# homeboard19.net
KiCad netlist of a schematic drawn in EAGLE
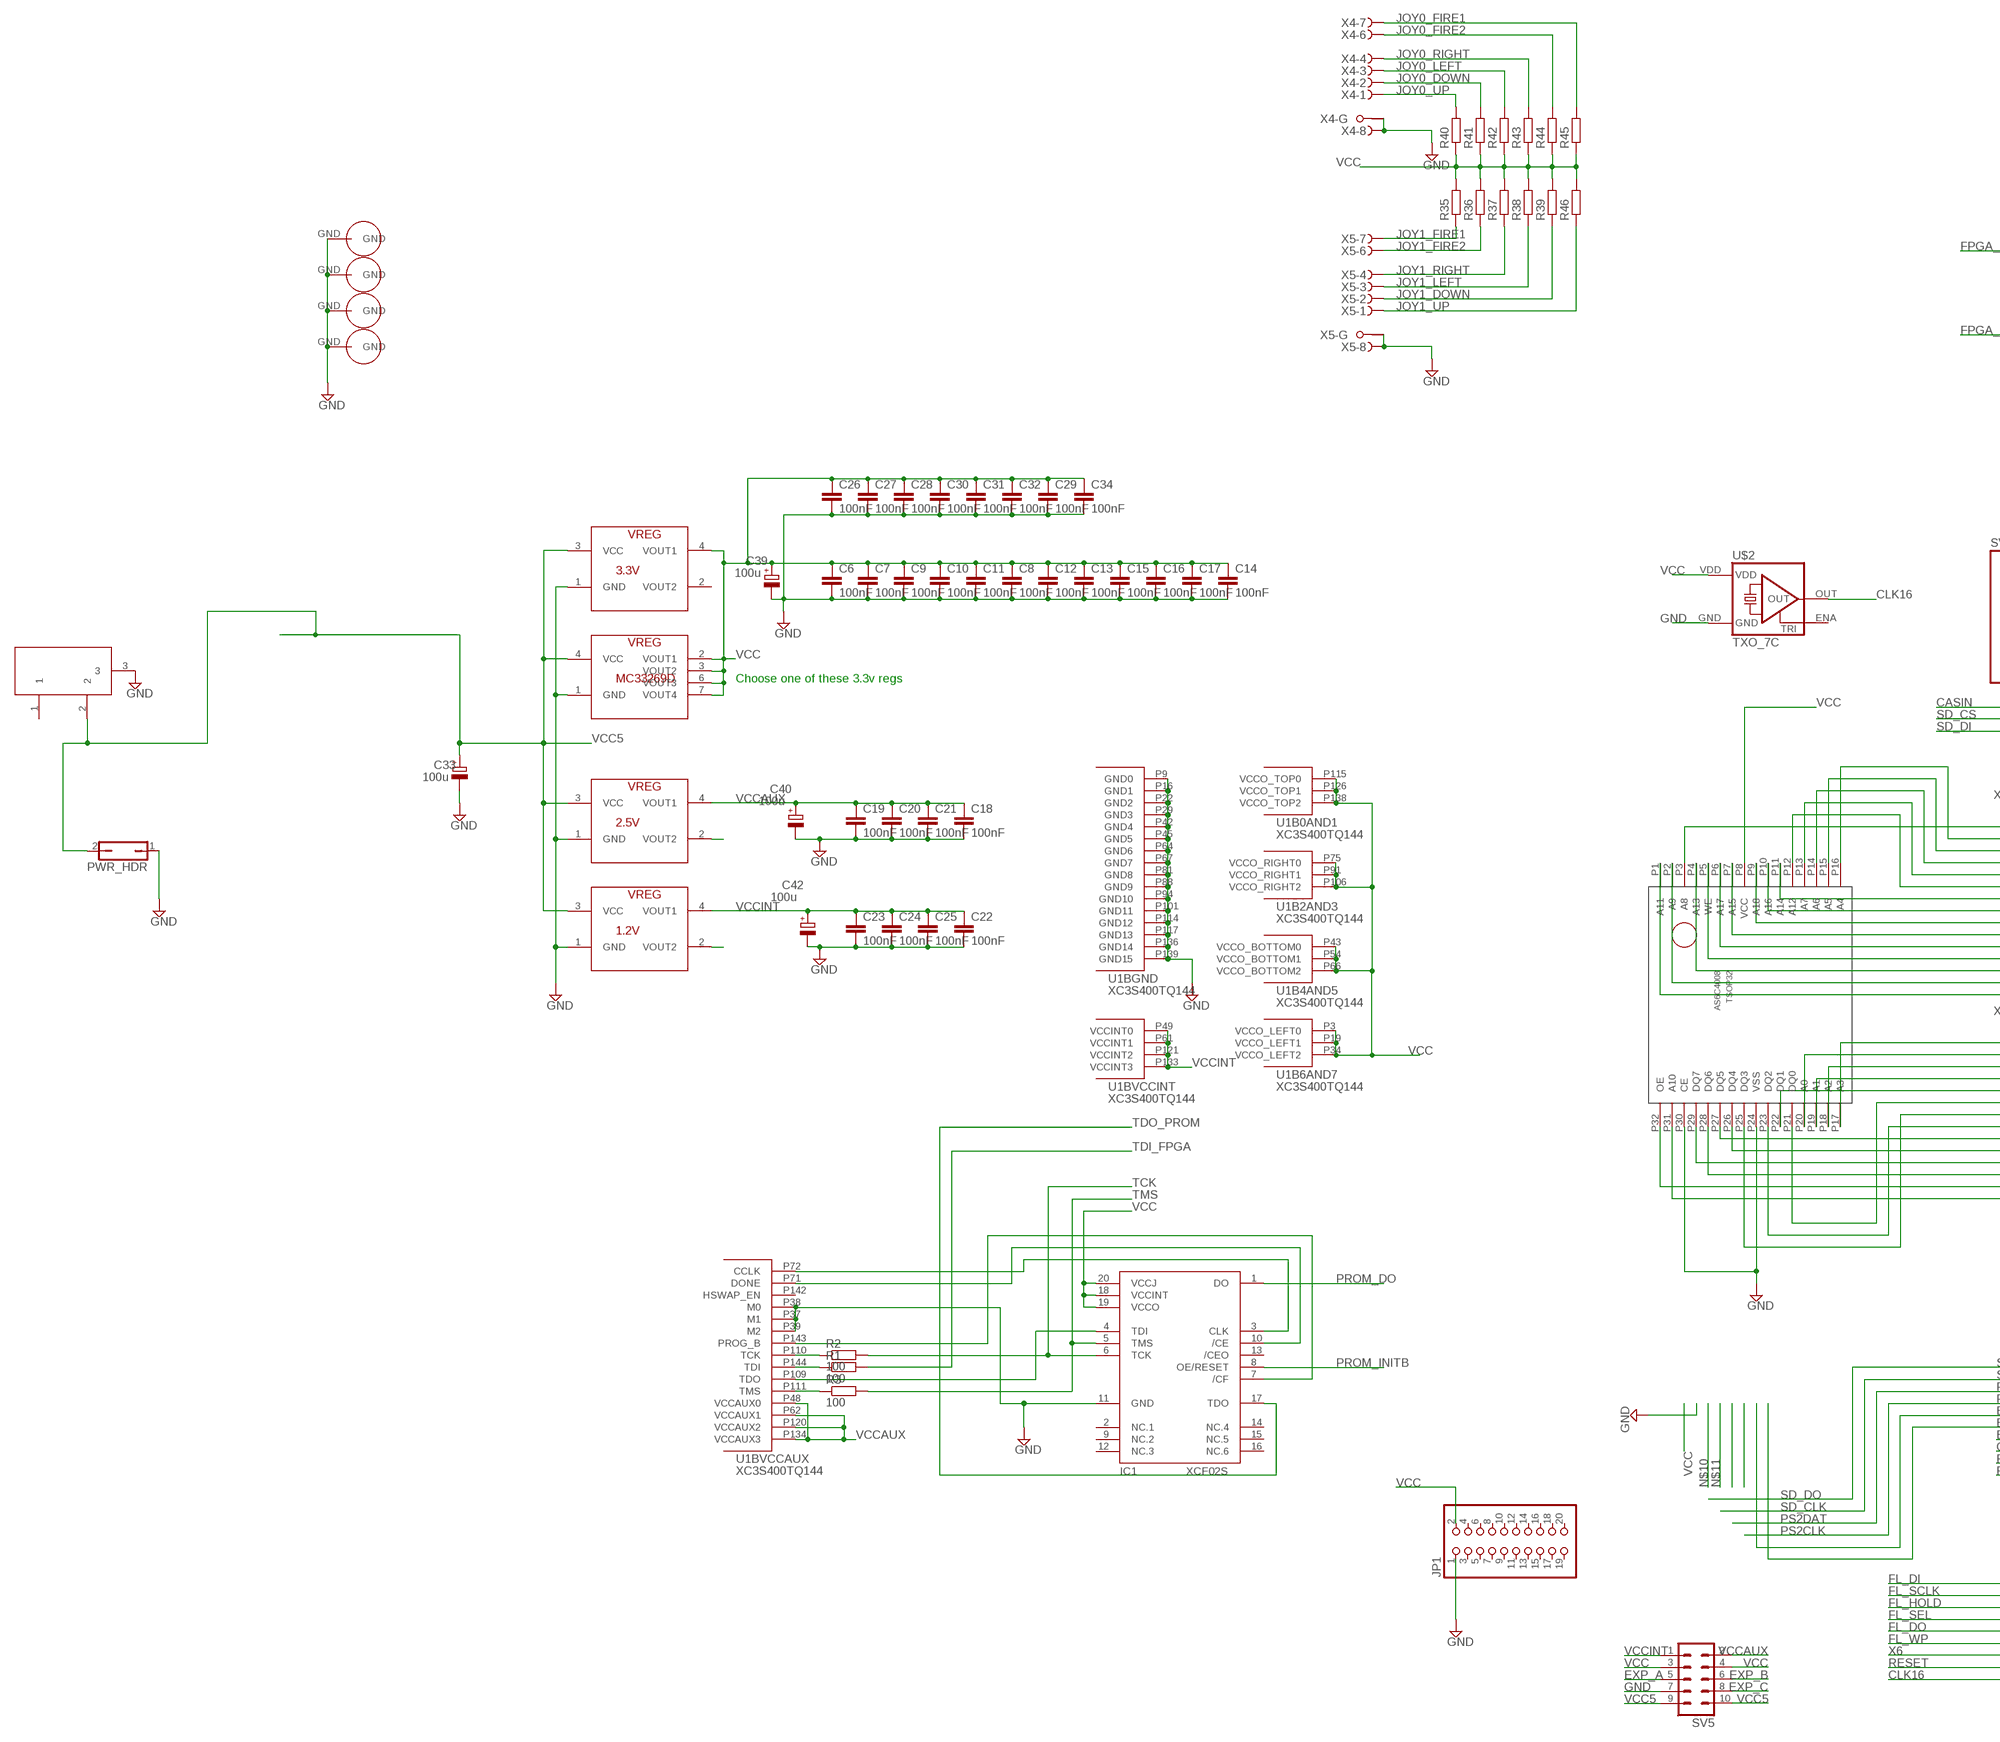
[diagram p0: schematic, sheet 1, part 1 of 3]
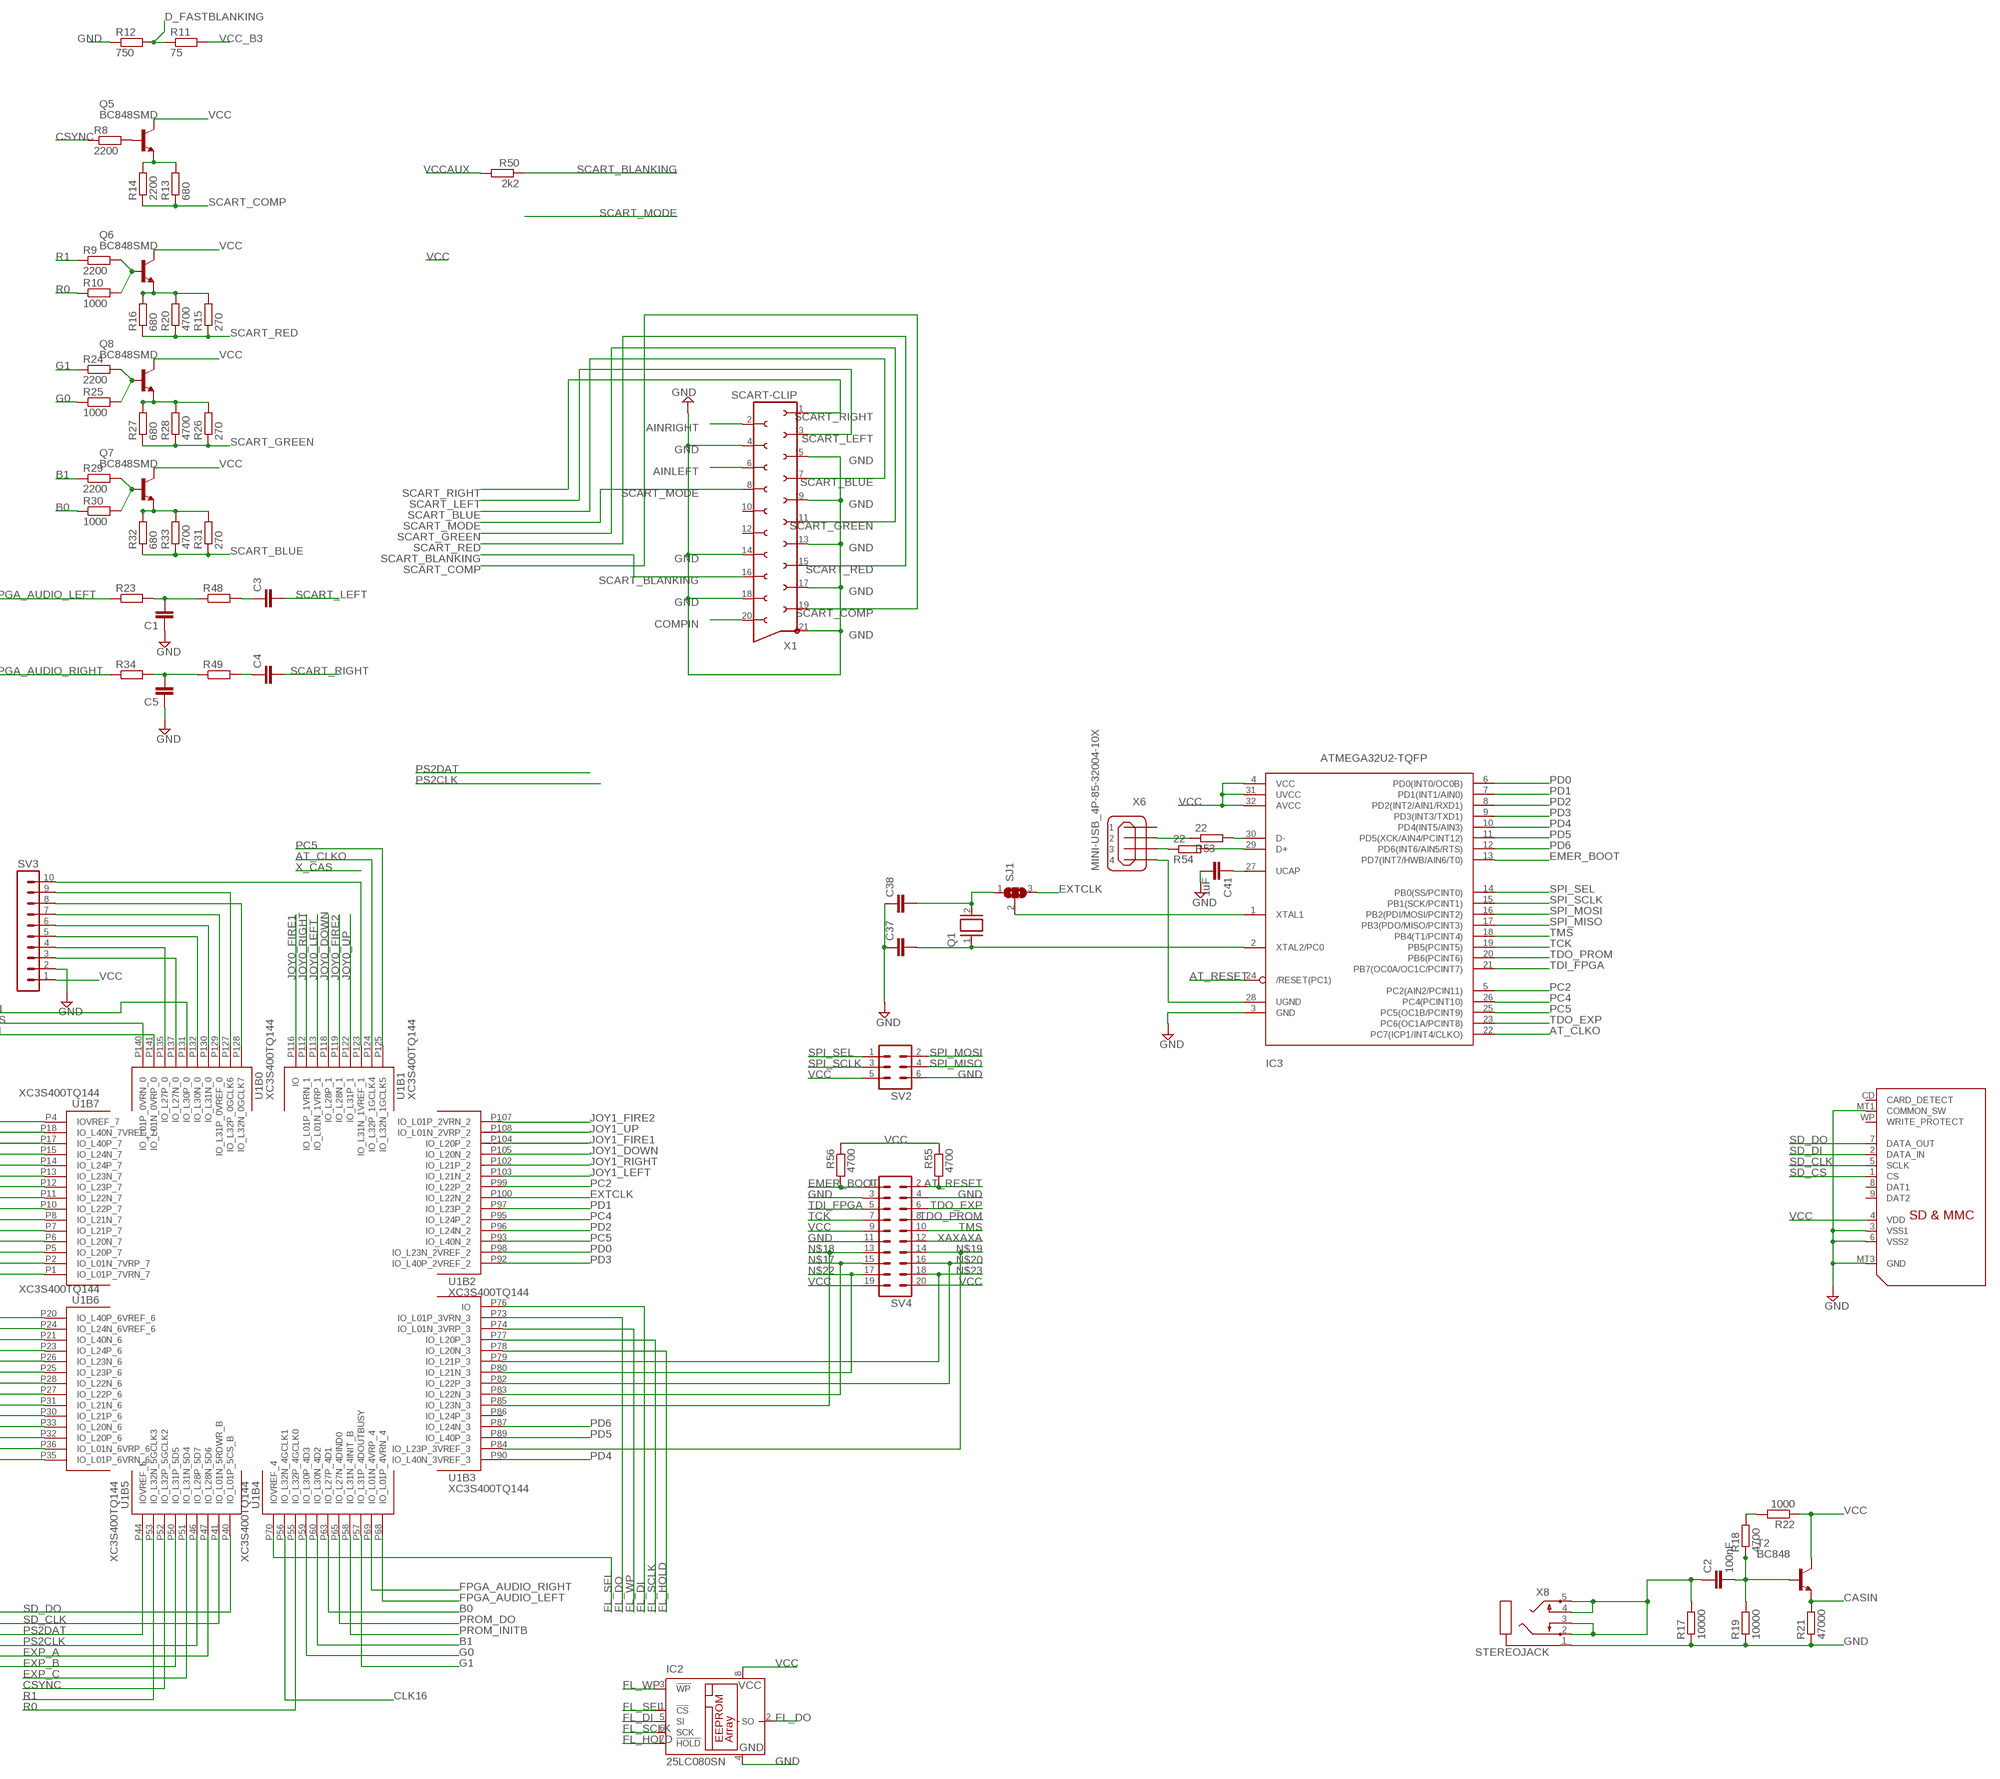
[diagram p1: schematic, sheet 1, part 2 of 3]
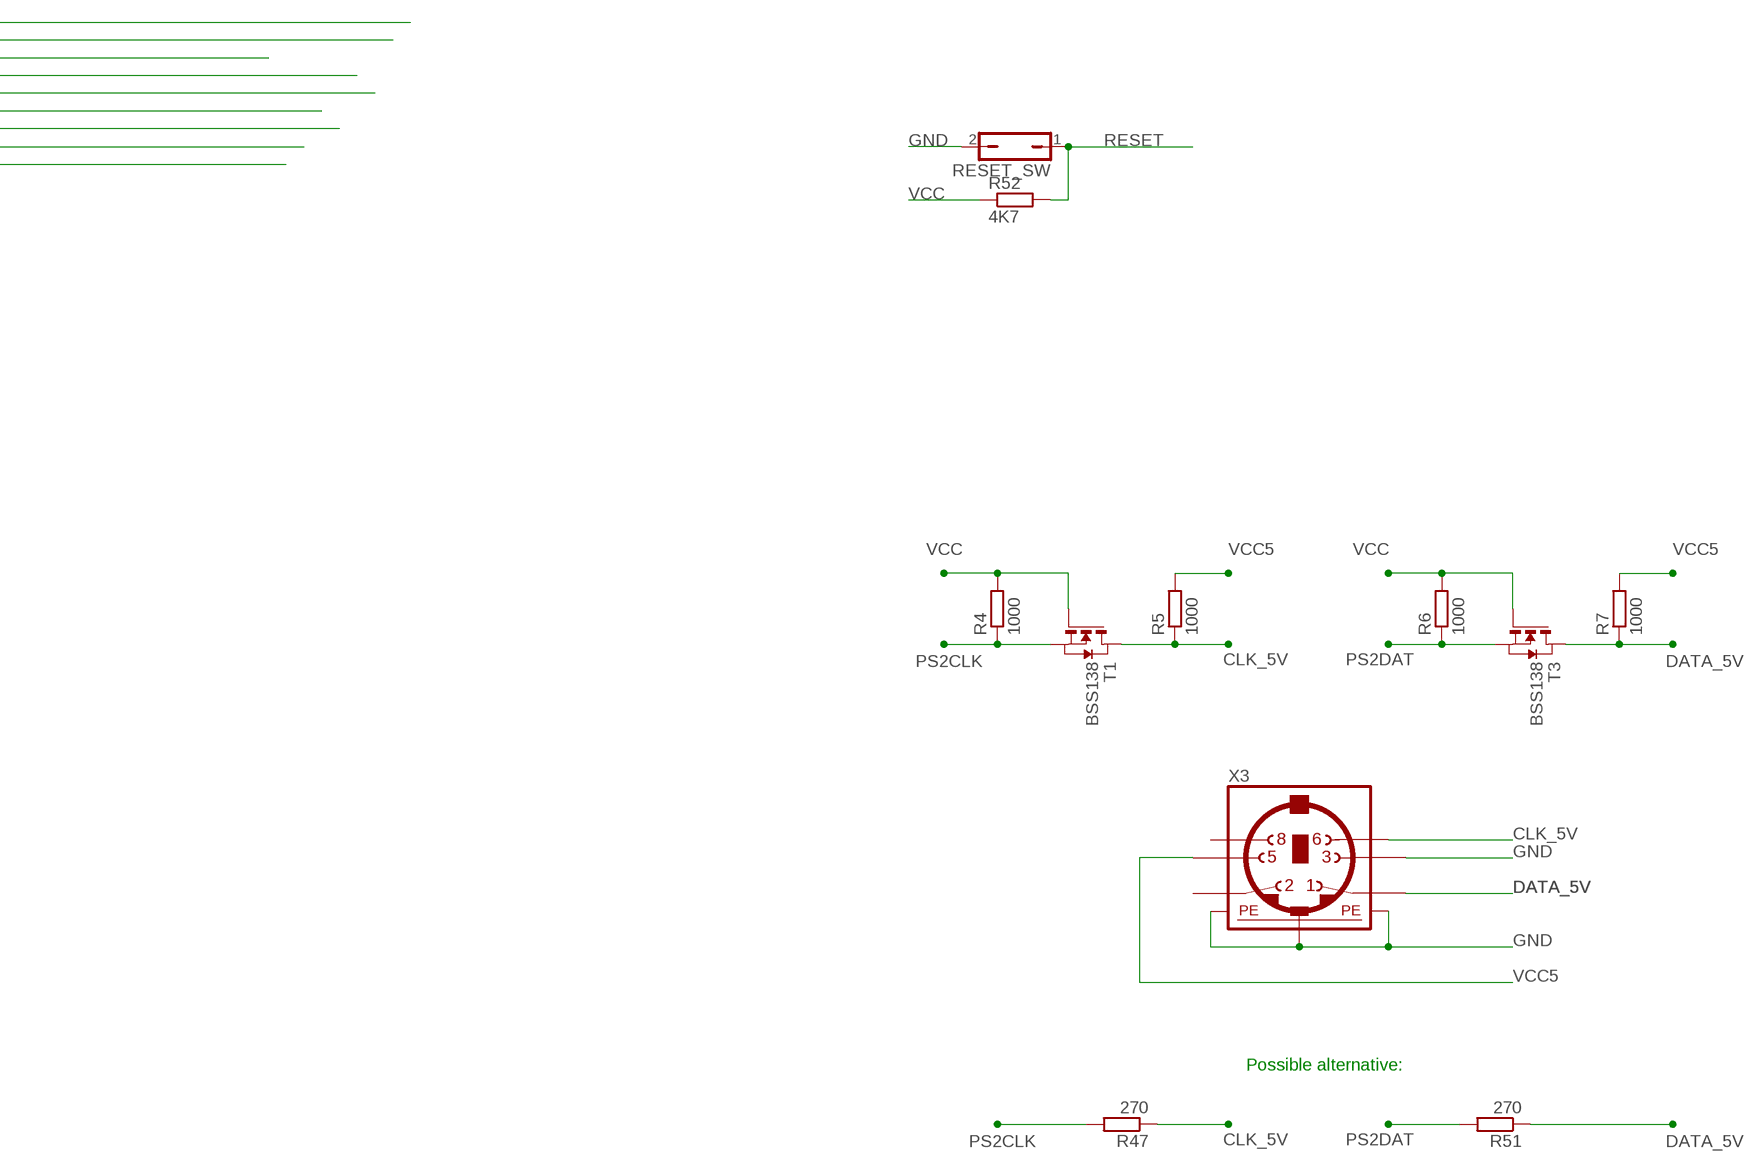
[diagram p2: schematic, sheet 1, part 3 of 3]

(export (version "E")
  (design (tool "Eeschema 10.0.6"))
  (components
    (comp (ref "C1")
      (value "C-EUC0603")
      (footprint "eagle-import:C0603")
      (libsource (lib "eagle-import") (part "resistor_C-EUC0603"))
    )
    (comp (ref "C2")
      (value "100nF")
      (footprint "eagle-import:C0603")
      (libsource (lib "eagle-import") (part "resistor_C-EUC0603"))
    )
    (comp (ref "C3")
      (value "C-EUC0603")
      (footprint "eagle-import:C0603")
      (libsource (lib "eagle-import") (part "resistor_C-EUC0603"))
    )
    (comp (ref "C4")
      (value "C-EUC0603")
      (footprint "eagle-import:C0603")
      (libsource (lib "eagle-import") (part "resistor_C-EUC0603"))
    )
    (comp (ref "C5")
      (value "C-EUC0603")
      (footprint "eagle-import:C0603")
      (libsource (lib "eagle-import") (part "resistor_C-EUC0603"))
    )
    (comp (ref "C6")
      (value "100nF")
      (footprint "eagle-import:C0603")
      (libsource (lib "eagle-import") (part "C-EUC0603"))
    )
    (comp (ref "C7")
      (value "100nF")
      (footprint "eagle-import:C0603")
      (libsource (lib "eagle-import") (part "C-EUC0603"))
    )
    (comp (ref "C8")
      (value "100nF")
      (footprint "eagle-import:C0603")
      (libsource (lib "eagle-import") (part "C-EUC0603"))
    )
    (comp (ref "C9")
      (value "100nF")
      (footprint "eagle-import:C0603")
      (libsource (lib "eagle-import") (part "C-EUC0603"))
    )
    (comp (ref "C10")
      (value "100nF")
      (footprint "eagle-import:C0603")
      (libsource (lib "eagle-import") (part "C-EUC0603"))
    )
    (comp (ref "C11")
      (value "100nF")
      (footprint "eagle-import:C0603")
      (libsource (lib "eagle-import") (part "C-EUC0603"))
    )
    (comp (ref "C12")
      (value "100nF")
      (footprint "eagle-import:C0603")
      (libsource (lib "eagle-import") (part "C-EUC0603"))
    )
    (comp (ref "C13")
      (value "100nF")
      (footprint "eagle-import:C0603")
      (libsource (lib "eagle-import") (part "C-EUC0603"))
    )
    (comp (ref "C14")
      (value "100nF")
      (footprint "eagle-import:C0603")
      (libsource (lib "eagle-import") (part "C-EUC0603"))
    )
    (comp (ref "C15")
      (value "100nF")
      (footprint "eagle-import:C0603")
      (libsource (lib "eagle-import") (part "C-EUC0603"))
    )
    (comp (ref "C16")
      (value "100nF")
      (footprint "eagle-import:C0603")
      (libsource (lib "eagle-import") (part "C-EUC0603"))
    )
    (comp (ref "C17")
      (value "100nF")
      (footprint "eagle-import:C0603")
      (libsource (lib "eagle-import") (part "C-EUC0603"))
    )
    (comp (ref "C18")
      (value "100nF")
      (footprint "eagle-import:C0603")
      (libsource (lib "eagle-import") (part "C-EUC0603"))
    )
    (comp (ref "C19")
      (value "100nF")
      (footprint "eagle-import:C0603")
      (libsource (lib "eagle-import") (part "C-EUC0603"))
    )
    (comp (ref "C20")
      (value "100nF")
      (footprint "eagle-import:C0603")
      (libsource (lib "eagle-import") (part "C-EUC0603"))
    )
    (comp (ref "C21")
      (value "100nF")
      (footprint "eagle-import:C0603")
      (libsource (lib "eagle-import") (part "C-EUC0603"))
    )
    (comp (ref "C22")
      (value "100nF")
      (footprint "eagle-import:C0603")
      (libsource (lib "eagle-import") (part "C-EUC0603"))
    )
    (comp (ref "C23")
      (value "100nF")
      (footprint "eagle-import:C0603")
      (libsource (lib "eagle-import") (part "C-EUC0603"))
    )
    (comp (ref "C24")
      (value "100nF")
      (footprint "eagle-import:C0603")
      (libsource (lib "eagle-import") (part "C-EUC0603"))
    )
    (comp (ref "C25")
      (value "100nF")
      (footprint "eagle-import:C0603")
      (libsource (lib "eagle-import") (part "C-EUC0603"))
    )
    (comp (ref "C26")
      (value "100nF")
      (footprint "eagle-import:C0603")
      (libsource (lib "eagle-import") (part "C-EUC0603"))
    )
    (comp (ref "C27")
      (value "100nF")
      (footprint "eagle-import:C0603")
      (libsource (lib "eagle-import") (part "C-EUC0603"))
    )
    (comp (ref "C28")
      (value "100nF")
      (footprint "eagle-import:C0603")
      (libsource (lib "eagle-import") (part "C-EUC0603"))
    )
    (comp (ref "C29")
      (value "100nF")
      (footprint "eagle-import:C0603")
      (libsource (lib "eagle-import") (part "C-EUC0603"))
    )
    (comp (ref "C30")
      (value "100nF")
      (footprint "eagle-import:C0603")
      (libsource (lib "eagle-import") (part "C-EUC0603"))
    )
    (comp (ref "C31")
      (value "100nF")
      (footprint "eagle-import:C0603")
      (libsource (lib "eagle-import") (part "C-EUC0603"))
    )
    (comp (ref "C32")
      (value "100nF")
      (footprint "eagle-import:C0603")
      (libsource (lib "eagle-import") (part "C-EUC0603"))
    )
    (comp (ref "C33")
      (value "100u")
      (footprint "eagle-import:PANASONIC_D")
      (libsource (lib "eagle-import") (part "CPOL-EUD"))
    )
    (comp (ref "C34")
      (value "100nF")
      (footprint "eagle-import:C0603")
      (libsource (lib "eagle-import") (part "C-EUC0603"))
    )
    (comp (ref "C37")
      (value "C-EUC0805")
      (footprint "eagle-import:C0805")
      (libsource (lib "eagle-import") (part "C-EUC0805"))
    )
    (comp (ref "C38")
      (value "C-EUC0805")
      (footprint "eagle-import:C0805")
      (libsource (lib "eagle-import") (part "C-EUC0805"))
    )
    (comp (ref "C39")
      (value "100u")
      (footprint "eagle-import:PANASONIC_D")
      (libsource (lib "eagle-import") (part "CPOL-EUD"))
    )
    (comp (ref "C40")
      (value "100u")
      (footprint "eagle-import:PANASONIC_D")
      (libsource (lib "eagle-import") (part "CPOL-EUD"))
    )
    (comp (ref "C41")
      (value "1uF")
      (footprint "eagle-import:C0805")
      (libsource (lib "eagle-import") (part "C-EUC0805"))
    )
    (comp (ref "C42")
      (value "100u")
      (footprint "eagle-import:PANASONIC_D")
      (libsource (lib "eagle-import") (part "CPOL-EUD"))
    )
    (comp (ref "IC1")
      (value "XCF02S")
      (footprint "eagle-import:VO20")
      (libsource (lib "eagle-import") (part "XCF02S"))
    )
    (comp (ref "IC2")
      (value "25LC080SN")
      (footprint "eagle-import:SO-08")
      (fields (field (name "MF") "MICROCHIP") (field (name "MPN") "25LC080/SN"))
      (libsource (lib "eagle-import") (part "25SNLC080"))
    )
    (comp (ref "IC3")
      (value "ATMEGA32U2-TQFP")
      (footprint "eagle-import:TQFP32-08")
      (libsource (lib "eagle-import") (part "ATMEGA32U2-TQFP"))
    )
    (comp (ref "JP1")
      (value "PINHD-2X10")
      (footprint "eagle-import:2X10")
      (libsource (lib "eagle-import") (part "PINHD-2X10"))
    )
    (comp (ref "PWR_HDR")
      (value "JP1Q")
      (footprint "eagle-import:JP1")
      (libsource (lib "eagle-import") (part "JP1Q"))
    )
    (comp (ref "Q1")
      (value "XTAL/S")
      (footprint "eagle-import:QS")
      (libsource (lib "eagle-import") (part "XTAL/S"))
    )
    (comp (ref "Q5")
      (value "BC848SMD")
      (footprint "eagle-import:SOT23")
      (libsource (lib "eagle-import") (part "BC848SMD"))
    )
    (comp (ref "Q6")
      (value "BC848SMD")
      (footprint "eagle-import:SOT23")
      (libsource (lib "eagle-import") (part "BC848SMD"))
    )
    (comp (ref "Q7")
      (value "BC848SMD")
      (footprint "eagle-import:SOT23")
      (libsource (lib "eagle-import") (part "BC848SMD"))
    )
    (comp (ref "Q8")
      (value "BC848SMD")
      (footprint "eagle-import:SOT23")
      (libsource (lib "eagle-import") (part "BC848SMD"))
    )
    (comp (ref "R1")
      (value "100")
      (footprint "eagle-import:R0805")
      (libsource (lib "eagle-import") (part "R-EU_R0805"))
    )
    (comp (ref "R2")
      (value "100")
      (footprint "eagle-import:R0805")
      (libsource (lib "eagle-import") (part "R-EU_R0805"))
    )
    (comp (ref "R3")
      (value "100")
      (footprint "eagle-import:R0805")
      (libsource (lib "eagle-import") (part "R-EU_R0805"))
    )
    (comp (ref "R4")
      (value "1000")
      (footprint "eagle-import:R0805")
      (libsource (lib "eagle-import") (part "R-EU_R0805"))
    )
    (comp (ref "R5")
      (value "1000")
      (footprint "eagle-import:R0805")
      (libsource (lib "eagle-import") (part "R-EU_R0805"))
    )
    (comp (ref "R6")
      (value "1000")
      (footprint "eagle-import:R0805")
      (libsource (lib "eagle-import") (part "R-EU_R0805"))
    )
    (comp (ref "R7")
      (value "1000")
      (footprint "eagle-import:R0805")
      (libsource (lib "eagle-import") (part "R-EU_R0805"))
    )
    (comp (ref "R8")
      (value "2200")
      (footprint "eagle-import:R0805")
      (libsource (lib "eagle-import") (part "R-EU_R0805"))
    )
    (comp (ref "R9")
      (value "2200")
      (footprint "eagle-import:R0805")
      (libsource (lib "eagle-import") (part "R-EU_R0805"))
    )
    (comp (ref "R10")
      (value "1000")
      (footprint "eagle-import:R0805")
      (libsource (lib "eagle-import") (part "R-EU_R0805"))
    )
    (comp (ref "R11")
      (value "75")
      (footprint "eagle-import:R0805")
      (libsource (lib "eagle-import") (part "R-EU_R0805"))
    )
    (comp (ref "R12")
      (value "750")
      (footprint "eagle-import:R0805")
      (libsource (lib "eagle-import") (part "R-EU_R0805"))
    )
    (comp (ref "R13")
      (value "680")
      (footprint "eagle-import:R0805")
      (libsource (lib "eagle-import") (part "R-EU_R0805"))
    )
    (comp (ref "R14")
      (value "2200")
      (footprint "eagle-import:R0805")
      (libsource (lib "eagle-import") (part "R-EU_R0805"))
    )
    (comp (ref "R15")
      (value "270")
      (footprint "eagle-import:R0805")
      (libsource (lib "eagle-import") (part "R-EU_R0805"))
    )
    (comp (ref "R16")
      (value "680")
      (footprint "eagle-import:R0805")
      (libsource (lib "eagle-import") (part "R-EU_R0805"))
    )
    (comp (ref "R17")
      (value "10000")
      (footprint "eagle-import:R0805")
      (libsource (lib "eagle-import") (part "R-EU_R0805"))
    )
    (comp (ref "R18")
      (value "4700")
      (footprint "eagle-import:R0805")
      (libsource (lib "eagle-import") (part "R-EU_R0805"))
    )
    (comp (ref "R19")
      (value "10000")
      (footprint "eagle-import:R0805")
      (libsource (lib "eagle-import") (part "R-EU_R0805"))
    )
    (comp (ref "R20")
      (value "4700")
      (footprint "eagle-import:R0805")
      (libsource (lib "eagle-import") (part "R-EU_R0805"))
    )
    (comp (ref "R21")
      (value "47000")
      (footprint "eagle-import:R0805")
      (libsource (lib "eagle-import") (part "R-EU_R0805"))
    )
    (comp (ref "R22")
      (value "1000")
      (footprint "eagle-import:R0805")
      (libsource (lib "eagle-import") (part "R-EU_R0805"))
    )
    (comp (ref "R23")
      (value "R-EU_M0805")
      (footprint "eagle-import:M0805")
      (libsource (lib "eagle-import") (part "resistor_R-EU_M0805"))
    )
    (comp (ref "R24")
      (value "2200")
      (footprint "eagle-import:R0805")
      (libsource (lib "eagle-import") (part "R-EU_R0805"))
    )
    (comp (ref "R25")
      (value "1000")
      (footprint "eagle-import:R0805")
      (libsource (lib "eagle-import") (part "R-EU_R0805"))
    )
    (comp (ref "R26")
      (value "270")
      (footprint "eagle-import:R0805")
      (libsource (lib "eagle-import") (part "R-EU_R0805"))
    )
    (comp (ref "R27")
      (value "680")
      (footprint "eagle-import:R0805")
      (libsource (lib "eagle-import") (part "R-EU_R0805"))
    )
    (comp (ref "R28")
      (value "4700")
      (footprint "eagle-import:R0805")
      (libsource (lib "eagle-import") (part "R-EU_R0805"))
    )
    (comp (ref "R29")
      (value "2200")
      (footprint "eagle-import:R0805")
      (libsource (lib "eagle-import") (part "R-EU_R0805"))
    )
    (comp (ref "R30")
      (value "1000")
      (footprint "eagle-import:R0805")
      (libsource (lib "eagle-import") (part "R-EU_R0805"))
    )
    (comp (ref "R31")
      (value "270")
      (footprint "eagle-import:R0805")
      (libsource (lib "eagle-import") (part "R-EU_R0805"))
    )
    (comp (ref "R32")
      (value "680")
      (footprint "eagle-import:R0805")
      (libsource (lib "eagle-import") (part "R-EU_R0805"))
    )
    (comp (ref "R33")
      (value "4700")
      (footprint "eagle-import:R0805")
      (libsource (lib "eagle-import") (part "R-EU_R0805"))
    )
    (comp (ref "R34")
      (value "R-EU_M0805")
      (footprint "eagle-import:M0805")
      (libsource (lib "eagle-import") (part "resistor_R-EU_M0805"))
    )
    (comp (ref "R35")
      (value "R-EU_M0805")
      (footprint "eagle-import:M0805")
      (libsource (lib "eagle-import") (part "resistor_R-EU_M0805"))
    )
    (comp (ref "R36")
      (value "R-EU_M0805")
      (footprint "eagle-import:M0805")
      (libsource (lib "eagle-import") (part "resistor_R-EU_M0805"))
    )
    (comp (ref "R37")
      (value "R-EU_M0805")
      (footprint "eagle-import:M0805")
      (libsource (lib "eagle-import") (part "resistor_R-EU_M0805"))
    )
    (comp (ref "R38")
      (value "R-EU_M0805")
      (footprint "eagle-import:M0805")
      (libsource (lib "eagle-import") (part "resistor_R-EU_M0805"))
    )
    (comp (ref "R39")
      (value "R-EU_M0805")
      (footprint "eagle-import:M0805")
      (libsource (lib "eagle-import") (part "resistor_R-EU_M0805"))
    )
    (comp (ref "R40")
      (value "R-EU_M0805")
      (footprint "eagle-import:M0805")
      (libsource (lib "eagle-import") (part "resistor_R-EU_M0805"))
    )
    (comp (ref "R41")
      (value "R-EU_M0805")
      (footprint "eagle-import:M0805")
      (libsource (lib "eagle-import") (part "resistor_R-EU_M0805"))
    )
    (comp (ref "R42")
      (value "R-EU_M0805")
      (footprint "eagle-import:M0805")
      (libsource (lib "eagle-import") (part "resistor_R-EU_M0805"))
    )
    (comp (ref "R43")
      (value "R-EU_M0805")
      (footprint "eagle-import:M0805")
      (libsource (lib "eagle-import") (part "resistor_R-EU_M0805"))
    )
    (comp (ref "R44")
      (value "R-EU_M0805")
      (footprint "eagle-import:M0805")
      (libsource (lib "eagle-import") (part "resistor_R-EU_M0805"))
    )
    (comp (ref "R45")
      (value "R-EU_M0805")
      (footprint "eagle-import:M0805")
      (libsource (lib "eagle-import") (part "resistor_R-EU_M0805"))
    )
    (comp (ref "R46")
      (value "R-EU_M0805")
      (footprint "eagle-import:M0805")
      (libsource (lib "eagle-import") (part "resistor_R-EU_M0805"))
    )
    (comp (ref "R47")
      (value "270")
      (footprint "eagle-import:R0805")
      (libsource (lib "eagle-import") (part "R-EU_R0805"))
    )
    (comp (ref "R48")
      (value "R-EU_M0805")
      (footprint "eagle-import:M0805")
      (libsource (lib "eagle-import") (part "resistor_R-EU_M0805"))
    )
    (comp (ref "R49")
      (value "R-EU_M0805")
      (footprint "eagle-import:M0805")
      (libsource (lib "eagle-import") (part "resistor_R-EU_M0805"))
    )
    (comp (ref "R50")
      (value "2k2")
      (footprint "eagle-import:M0805")
      (libsource (lib "eagle-import") (part "resistor_R-EU_M0805"))
    )
    (comp (ref "R51")
      (value "270")
      (footprint "eagle-import:R0805")
      (libsource (lib "eagle-import") (part "R-EU_R0805"))
    )
    (comp (ref "R52")
      (value "4K7")
      (footprint "eagle-import:M0805")
      (libsource (lib "eagle-import") (part "resistor_R-EU_M0805"))
    )
    (comp (ref "R53")
      (value "22")
      (footprint "eagle-import:R0805")
      (libsource (lib "eagle-import") (part "R-EU_R0805"))
    )
    (comp (ref "R54")
      (value "22")
      (footprint "eagle-import:R0805")
      (libsource (lib "eagle-import") (part "R-EU_R0805"))
    )
    (comp (ref "R55")
      (value "4700")
      (footprint "eagle-import:R0805")
      (libsource (lib "eagle-import") (part "R-EU_R0805"))
    )
    (comp (ref "R56")
      (value "4700")
      (footprint "eagle-import:R0805")
      (libsource (lib "eagle-import") (part "R-EU_R0805"))
    )
    (comp (ref "REG1.2")
      (value "1.2V")
      (footprint "eagle-import:SOT223")
      (libsource (lib "eagle-import") (part "NX1117"))
    )
    (comp (ref "REG2.5")
      (value "2.5V")
      (footprint "eagle-import:SOT223")
      (libsource (lib "eagle-import") (part "NX1117"))
    )
    (comp (ref "RESET_SW")
      (value "JP1Q")
      (footprint "eagle-import:JP1")
      (libsource (lib "eagle-import") (part "JP1Q"))
    )
    (comp (ref "SJ1")
      (value "SJ2W")
      (footprint "eagle-import:SJ_2")
      (libsource (lib "eagle-import") (part "SJ2W"))
    )
    (comp (ref "SV2")
      (value "MA03-2")
      (footprint "eagle-import:MA03-2")
      (libsource (lib "eagle-import") (part "MA03-2"))
    )
    (comp (ref "SV3")
      (value "MA10-1")
      (footprint "eagle-import:MA10-1")
      (libsource (lib "eagle-import") (part "MA10-1"))
    )
    (comp (ref "SV4")
      (value "MA10-2")
      (footprint "eagle-import:MA10-2")
      (libsource (lib "eagle-import") (part "MA10-2"))
    )
    (comp (ref "SV5")
      (value "MA05-2")
      (footprint "eagle-import:MA05-2")
      (libsource (lib "eagle-import") (part "MA05-2"))
    )
    (comp (ref "T1")
      (value "BSS138")
      (footprint "eagle-import:SOT-23")
      (libsource (lib "eagle-import") (part "NMOSSOT23"))
    )
    (comp (ref "T2")
      (value "BC848")
      (footprint "eagle-import:SOT23")
      (libsource (lib "eagle-import") (part "BC848"))
    )
    (comp (ref "T3")
      (value "BSS138")
      (footprint "eagle-import:SOT-23")
      (libsource (lib "eagle-import") (part "NMOSSOT23"))
    )
    (comp (ref "U$1")
      (value "GNDHOLE")
      (footprint "eagle-import:GNDHOLE")
      (libsource (lib "eagle-import") (part "GNDHOLE"))
    )
    (comp (ref "U$2")
      (value "TXO_7C")
      (footprint "eagle-import:OSC_7C")
      (libsource (lib "eagle-import") (part "TXO_7C"))
    )
    (comp (ref "U$3")
      (value "SDMMCNOHOLE")
      (footprint "eagle-import:SDCARD-NOHOLE")
      (libsource (lib "eagle-import") (part "SDMMCNOHOLE"))
    )
    (comp (ref "U$4")
      (value "3.3V")
      (footprint "eagle-import:SOT223")
      (libsource (lib "eagle-import") (part "NX1117"))
    )
    (comp (ref "U$5")
      (value "MC33269D")
      (footprint "eagle-import:SO8")
      (libsource (lib "eagle-import") (part "MC33269D"))
    )
    (comp (ref "U$6")
      (value "AS6C4008")
      (footprint "eagle-import:TSOP32")
      (libsource (lib "eagle-import") (part "AS6C4008"))
    )
    (comp (ref "U$7")
      (value "GNDHOLE")
      (footprint "eagle-import:GNDHOLE")
      (libsource (lib "eagle-import") (part "GNDHOLE"))
    )
    (comp (ref "U$8")
      (value "GNDHOLE")
      (footprint "eagle-import:GNDHOLE")
      (libsource (lib "eagle-import") (part "GNDHOLE"))
    )
    (comp (ref "U$9")
      (value "GNDHOLE")
      (footprint "eagle-import:GNDHOLE")
      (libsource (lib "eagle-import") (part "GNDHOLE"))
    )
    (comp (ref "U1")
      (value "XC3S400TQ144")
      (footprint "eagle-import:TQ144")
      (libsource (lib "eagle-import") (part "XC3S400TQ144"))
    )
    (comp (ref "X1")
      (value "SCART-CLIP")
      (footprint "eagle-import:SCART-CLIP")
      (libsource (lib "eagle-import") (part "SCART-CLIP"))
    )
    (comp (ref "X3")
      (value "MINI_DIN_6")
      (footprint "eagle-import:M_DIN6")
      (libsource (lib "eagle-import") (part "MINI_DIN_6"))
    )
    (comp (ref "X4")
      (value "F09HPS")
      (footprint "eagle-import:F09HP")
      (libsource (lib "eagle-import") (part "F09HPS"))
    )
    (comp (ref "X5")
      (value "F09HPS")
      (footprint "eagle-import:F09HP")
      (libsource (lib "eagle-import") (part "F09HPS"))
    )
    (comp (ref "X6")
      (value "MINI-USB_4P-85-32004-10X")
      (footprint "eagle-import:85-32004-10X")
      (libsource (lib "eagle-import") (part "MINI-USB_4P-85-32004-10X"))
    )
    (comp (ref "X7")
      (value "DC21MMX")
      (footprint "eagle-import:DC-21MM")
      (libsource (lib "eagle-import") (part "DC21MMX"))
    )
    (comp (ref "X8")
      (value "STEREOJACK")
      (footprint "eagle-import:20-0137")
      (libsource (lib "eagle-import") (part "STEREOJACK"))
    )
  )
  (nets
    (net (code "1") (name "/1") (class "Default")
      (node (ref "X7") (pin "1") (pinfunction "1_1") (pintype "power_in"))
    )
    (net (code "2") (name "/AINLEFT") (class "Default")
      (node (ref "X1") (pin "6") (pinfunction "6_6") (pintype "passive"))
    )
    (net (code "3") (name "/AINRIGHT") (class "Default")
      (node (ref "X1") (pin "2") (pinfunction "2_2") (pintype "passive"))
    )
    (net (code "4") (name "/AT_CLKO") (class "Default")
      (node (ref "IC3") (pin "22") (pinfunction "PC7(ICP1/INT4/CLKO)_22") (pintype "bidirectional"))
      (node (ref "U1") (pin "P124") (pinfunction "IO_L32P_1GCLK4_P124") (pintype "bidirectional"))
    )
    (net (code "5") (name "/AT_RESET") (class "Default")
      (node (ref "IC3") (pin "24") (pinfunction "/RESET(PC1)_24") (pintype "bidirectional"))
      (node (ref "R55") (pin "2") (pinfunction "2_2") (pintype "passive"))
      (node (ref "SV4") (pin "2") (pinfunction "2_2") (pintype "passive"))
    )
    (net (code "6") (name "/B0") (class "Default")
      (node (ref "R30") (pin "1") (pinfunction "1_1") (pintype "passive"))
      (node (ref "U1") (pin "P63") (pinfunction "IO_L27P_4D1_P63") (pintype "bidirectional"))
    )
    (net (code "7") (name "/B1") (class "Default")
      (node (ref "R29") (pin "1") (pinfunction "1_1") (pintype "passive"))
      (node (ref "U1") (pin "P60") (pinfunction "IO_L30N_4D2_P60") (pintype "bidirectional"))
    )
    (net (code "8") (name "/CASIN") (class "Default")
      (node (ref "R21") (pin "2") (pinfunction "2_2") (pintype "passive"))
      (node (ref "T2") (pin "2") (pinfunction "E_2") (pintype "passive"))
      (node (ref "U1") (pin "P131") (pinfunction "IO_L30P_0_P131") (pintype "bidirectional"))
    )
    (net (code "9") (name "/CLK16") (class "Default")
      (node (ref "U$2") (pin "OUT") (pinfunction "OUT_OUT") (pintype "output"))
      (node (ref "U1") (pin "P56") (pinfunction "IO_L32N_4GCLK1_P56") (pintype "bidirectional"))
    )
    (net (code "10") (name "/CLK_5V") (class "Default")
      (node (ref "R47") (pin "1") (pinfunction "1_1") (pintype "passive"))
      (node (ref "R5") (pin "1") (pinfunction "1_1") (pintype "passive"))
      (node (ref "T1") (pin "1") (pinfunction "D_1") (pintype "passive"))
      (node (ref "X3") (pin "6") (pinfunction "6_6") (pintype "passive"))
    )
    (net (code "11") (name "/COMPIN") (class "Default")
      (node (ref "X1") (pin "20") (pinfunction "20_20") (pintype "passive"))
    )
    (net (code "12") (name "/CSYNC") (class "Default")
      (node (ref "R8") (pin "1") (pinfunction "1_1") (pintype "passive"))
      (node (ref "U1") (pin "P52") (pinfunction "IO_L32P_5GCLK2_P52") (pintype "bidirectional"))
    )
    (net (code "13") (name "/DATA_5V") (class "Default")
      (node (ref "R51") (pin "1") (pinfunction "1_1") (pintype "passive"))
      (node (ref "R7") (pin "1") (pinfunction "1_1") (pintype "passive"))
      (node (ref "T3") (pin "1") (pinfunction "D_1") (pintype "passive"))
      (node (ref "X3") (pin "1") (pinfunction "1_1") (pintype "passive"))
    )
    (net (code "14") (name "/D_FASTBLANKING") (class "Default")
      (node (ref "R11") (pin "1") (pinfunction "1_1") (pintype "passive"))
      (node (ref "R12") (pin "2") (pinfunction "2_2") (pintype "passive"))
    )
    (net (code "15") (name "/EMER_BOOT") (class "Default")
      (node (ref "IC3") (pin "13") (pinfunction "PD7(INT7/HWB/AIN6/T0)_13") (pintype "bidirectional"))
      (node (ref "R56") (pin "2") (pinfunction "2_2") (pintype "passive"))
      (node (ref "SV4") (pin "1") (pinfunction "1_1") (pintype "passive"))
    )
    (net (code "16") (name "/EXP_A") (class "Default")
      (node (ref "SV5") (pin "5") (pinfunction "5_5") (pintype "passive"))
      (node (ref "U1") (pin "P47") (pinfunction "IO_L28N_5D6_P47") (pintype "bidirectional"))
    )
    (net (code "17") (name "/EXP_B") (class "Default")
      (node (ref "SV5") (pin "6") (pinfunction "6_6") (pintype "passive"))
      (node (ref "U1") (pin "P50") (pinfunction "IO_L31P_5D5_P50") (pintype "bidirectional"))
    )
    (net (code "18") (name "/EXP_C") (class "Default")
      (node (ref "SV5") (pin "8") (pinfunction "8_8") (pintype "passive"))
      (node (ref "U1") (pin "P51") (pinfunction "IO_L31N_5D4_P51") (pintype "bidirectional"))
    )
    (net (code "19") (name "/EXTCLK") (class "Default")
      (node (ref "SJ1") (pin "3") (pinfunction "3_3") (pintype "passive"))
      (node (ref "U1") (pin "P100") (pinfunction "IO_L22N_2_P100") (pintype "bidirectional"))
    )
    (net (code "20") (name "/FL_DI") (class "Default")
      (node (ref "IC2") (pin "5") (pinfunction "SI_5") (pintype "input"))
      (node (ref "U1") (pin "P76") (pinfunction "IO_P76") (pintype "bidirectional"))
    )
    (net (code "21") (name "/FL_DO") (class "Default")
      (node (ref "IC2") (pin "2") (pinfunction "SO_2") (pintype "bidirectional"))
      (node (ref "U1") (pin "P73") (pinfunction "IO_L01P_3VRN_3_P73") (pintype "bidirectional"))
    )
    (net (code "22") (name "/FL_HOLD") (class "Default")
      (node (ref "IC2") (pin "7") (pinfunction "~{HOLD}_7") (pintype "input"))
      (node (ref "U1") (pin "P78") (pinfunction "IO_L20N_3_P78") (pintype "bidirectional"))
    )
    (net (code "23") (name "/FL_SCLK") (class "Default")
      (node (ref "IC2") (pin "6") (pinfunction "SCK_6") (pintype "input"))
      (node (ref "U1") (pin "P77") (pinfunction "IO_L20P_3_P77") (pintype "bidirectional"))
    )
    (net (code "24") (name "/FL_SEL") (class "Default")
      (node (ref "IC2") (pin "1") (pinfunction "~{CS}_1") (pintype "input"))
      (node (ref "U1") (pin "P70") (pinfunction "IOVREF_4_P70") (pintype "bidirectional"))
    )
    (net (code "25") (name "/FL_WP") (class "Default")
      (node (ref "IC2") (pin "3") (pinfunction "~{WP}_3") (pintype "input"))
      (node (ref "U1") (pin "P74") (pinfunction "IO_L01N_3VRP_3_P74") (pintype "bidirectional"))
    )
    (net (code "26") (name "/FPGA_AUDIO_LEFT") (class "Default")
      (node (ref "R23") (pin "1") (pinfunction "1_1") (pintype "passive"))
      (node (ref "U1") (pin "P68") (pinfunction "IO_L01P_4VRN_4_P68") (pintype "bidirectional"))
    )
    (net (code "27") (name "/FPGA_AUDIO_RIGHT") (class "Default")
      (node (ref "R34") (pin "1") (pinfunction "1_1") (pintype "passive"))
      (node (ref "U1") (pin "P69") (pinfunction "IO_L01N_4VRP_4_P69") (pintype "bidirectional"))
    )
    (net (code "28") (name "/G0") (class "Default")
      (node (ref "R25") (pin "1") (pinfunction "1_1") (pintype "passive"))
      (node (ref "U1") (pin "P59") (pinfunction "IO_L30P_4D3_P59") (pintype "bidirectional"))
    )
    (net (code "29") (name "/G1") (class "Default")
      (node (ref "R24") (pin "1") (pinfunction "1_1") (pintype "passive"))
      (node (ref "U1") (pin "P57") (pinfunction "IO_L31P_4DOUTBUSY_P57") (pintype "bidirectional"))
    )
    (net (code "30") (name "/JOY0_DOWN") (class "Default")
      (node (ref "R41") (pin "2") (pinfunction "2_2") (pintype "passive"))
      (node (ref "U1") (pin "P118") (pinfunction "IO_L28P_1_P118") (pintype "bidirectional"))
      (node (ref "X4") (pin "2") (pinfunction "F_2") (pintype "passive"))
    )
    (net (code "31") (name "/JOY0_FIRE1") (class "Default")
      (node (ref "R45") (pin "2") (pinfunction "2_2") (pintype "passive"))
      (node (ref "U1") (pin "P116") (pinfunction "IO_P116") (pintype "bidirectional"))
      (node (ref "X4") (pin "7") (pinfunction "F_7") (pintype "passive"))
    )
    (net (code "32") (name "/JOY0_FIRE2") (class "Default")
      (node (ref "R44") (pin "2") (pinfunction "2_2") (pintype "passive"))
      (node (ref "U1") (pin "P119") (pinfunction "IO_L28N_1_P119") (pintype "bidirectional"))
      (node (ref "X4") (pin "6") (pinfunction "F_6") (pintype "passive"))
    )
    (net (code "33") (name "/JOY0_LEFT") (class "Default")
      (node (ref "R42") (pin "2") (pinfunction "2_2") (pintype "passive"))
      (node (ref "U1") (pin "P113") (pinfunction "IO_L01N_1VRP_1_P113") (pintype "bidirectional"))
      (node (ref "X4") (pin "3") (pinfunction "F_3") (pintype "passive"))
    )
    (net (code "34") (name "/JOY0_RIGHT") (class "Default")
      (node (ref "R43") (pin "2") (pinfunction "2_2") (pintype "passive"))
      (node (ref "U1") (pin "P112") (pinfunction "IO_L01P_1VRN_1_P112") (pintype "bidirectional"))
      (node (ref "X4") (pin "4") (pinfunction "F_4") (pintype "passive"))
    )
    (net (code "35") (name "/JOY0_UP") (class "Default")
      (node (ref "R40") (pin "2") (pinfunction "2_2") (pintype "passive"))
      (node (ref "U1") (pin "P122") (pinfunction "IO_L31P_1_P122") (pintype "bidirectional"))
      (node (ref "X4") (pin "1") (pinfunction "F_1") (pintype "passive"))
    )
    (net (code "36") (name "/JOY1_DOWN") (class "Default")
      (node (ref "R39") (pin "1") (pinfunction "1_1") (pintype "passive"))
      (node (ref "U1") (pin "P105") (pinfunction "IO_L20N_2_P105") (pintype "bidirectional"))
      (node (ref "X5") (pin "2") (pinfunction "F_2") (pintype "passive"))
    )
    (net (code "37") (name "/JOY1_FIRE1") (class "Default")
      (node (ref "R35") (pin "1") (pinfunction "1_1") (pintype "passive"))
      (node (ref "U1") (pin "P104") (pinfunction "IO_L20P_2_P104") (pintype "bidirectional"))
      (node (ref "X5") (pin "7") (pinfunction "F_7") (pintype "passive"))
    )
    (net (code "38") (name "/JOY1_FIRE2") (class "Default")
      (node (ref "R36") (pin "1") (pinfunction "1_1") (pintype "passive"))
      (node (ref "U1") (pin "P107") (pinfunction "IO_L01P_2VRN_2_P107") (pintype "bidirectional"))
      (node (ref "X5") (pin "6") (pinfunction "F_6") (pintype "passive"))
    )
    (net (code "39") (name "/JOY1_LEFT") (class "Default")
      (node (ref "R38") (pin "1") (pinfunction "1_1") (pintype "passive"))
      (node (ref "U1") (pin "P103") (pinfunction "IO_L21N_2_P103") (pintype "bidirectional"))
      (node (ref "X5") (pin "3") (pinfunction "F_3") (pintype "passive"))
    )
    (net (code "40") (name "/JOY1_RIGHT") (class "Default")
      (node (ref "R37") (pin "1") (pinfunction "1_1") (pintype "passive"))
      (node (ref "U1") (pin "P102") (pinfunction "IO_L21P_2_P102") (pintype "bidirectional"))
      (node (ref "X5") (pin "4") (pinfunction "F_4") (pintype "passive"))
    )
    (net (code "41") (name "/JOY1_UP") (class "Default")
      (node (ref "R46") (pin "1") (pinfunction "1_1") (pintype "passive"))
      (node (ref "U1") (pin "P108") (pinfunction "IO_L01N_2VRP_2_P108") (pintype "bidirectional"))
      (node (ref "X5") (pin "1") (pinfunction "F_1") (pintype "passive"))
    )
    (net (code "44") (name "/N$17") (class "Default")
      (node (ref "SV4") (pin "15") (pinfunction "15_15") (pintype "passive"))
      (node (ref "U1") (pin "P83") (pinfunction "IO_L22N_3_P83") (pintype "bidirectional"))
    )
    (net (code "45") (name "/N$18") (class "Default")
      (node (ref "SV4") (pin "13") (pinfunction "13_13") (pintype "passive"))
      (node (ref "U1") (pin "P85") (pinfunction "IO_L23N_3_P85") (pintype "bidirectional"))
    )
    (net (code "46") (name "/N$19") (class "Default")
      (node (ref "SV4") (pin "14") (pinfunction "14_14") (pintype "passive"))
      (node (ref "U1") (pin "P84") (pinfunction "IO_L23P_3VREF_3_P84") (pintype "bidirectional"))
    )
    (net (code "47") (name "/N$20") (class "Default")
      (node (ref "SV4") (pin "16") (pinfunction "16_16") (pintype "passive"))
      (node (ref "U1") (pin "P82") (pinfunction "IO_L22P_3_P82") (pintype "bidirectional"))
    )
    (net (code "48") (name "/N$22") (class "Default")
      (node (ref "SV4") (pin "17") (pinfunction "17_17") (pintype "passive"))
      (node (ref "U1") (pin "P80") (pinfunction "IO_L21N_3_P80") (pintype "bidirectional"))
    )
    (net (code "49") (name "/N$23") (class "Default")
      (node (ref "SV4") (pin "18") (pinfunction "18_18") (pintype "passive"))
      (node (ref "U1") (pin "P79") (pinfunction "IO_L21P_3_P79") (pintype "bidirectional"))
    )
    (net (code "50") (name "/PC2") (class "Default")
      (node (ref "IC3") (pin "5") (pinfunction "PC2(AIN2/PCIN11)_5") (pintype "bidirectional"))
      (node (ref "U1") (pin "P99") (pinfunction "IO_L22P_2_P99") (pintype "bidirectional"))
    )
    (net (code "51") (name "/PC4") (class "Default")
      (node (ref "IC3") (pin "26") (pinfunction "PC4(PCINT10)_26") (pintype "bidirectional"))
      (node (ref "U1") (pin "P95") (pinfunction "IO_L24P_2_P95") (pintype "bidirectional"))
    )
    (net (code "52") (name "/PC5") (class "Default")
      (node (ref "IC3") (pin "25") (pinfunction "PC5(OC1B/PCINT9)_25") (pintype "bidirectional"))
      (node (ref "U1") (pin "P125") (pinfunction "IO_L32N_1GCLK5_P125") (pintype "bidirectional"))
      (node (ref "U1") (pin "P93") (pinfunction "IO_L40N_2_P93") (pintype "bidirectional"))
    )
    (net (code "53") (name "/PD0") (class "Default")
      (node (ref "IC3") (pin "6") (pinfunction "PD0(INT0/OC0B)_6") (pintype "bidirectional"))
      (node (ref "U1") (pin "P98") (pinfunction "IO_L23N_2VREF_2_P98") (pintype "bidirectional"))
    )
    (net (code "54") (name "/PD1") (class "Default")
      (node (ref "IC3") (pin "7") (pinfunction "PD1(INT1/AIN0)_7") (pintype "bidirectional"))
      (node (ref "U1") (pin "P97") (pinfunction "IO_L23P_2_P97") (pintype "bidirectional"))
    )
    (net (code "55") (name "/PD2") (class "Default")
      (node (ref "IC3") (pin "8") (pinfunction "PD2(INT2/AIN1/RXD1)_8") (pintype "bidirectional"))
      (node (ref "U1") (pin "P96") (pinfunction "IO_L24N_2_P96") (pintype "bidirectional"))
    )
    (net (code "56") (name "/PD3") (class "Default")
      (node (ref "IC3") (pin "9") (pinfunction "PD3(INT3/TXD1)_9") (pintype "bidirectional"))
      (node (ref "U1") (pin "P92") (pinfunction "IO_L40P_2VREF_2_P92") (pintype "bidirectional"))
    )
    (net (code "57") (name "/PD4") (class "Default")
      (node (ref "IC3") (pin "10") (pinfunction "PD4(INT5/AIN3)_10") (pintype "bidirectional"))
      (node (ref "U1") (pin "P90") (pinfunction "IO_L40N_3VREF_3_P90") (pintype "bidirectional"))
    )
    (net (code "58") (name "/PD5") (class "Default")
      (node (ref "IC3") (pin "11") (pinfunction "PD5(XCK/AIN4/PCINT12)_11") (pintype "bidirectional"))
      (node (ref "U1") (pin "P89") (pinfunction "IO_L40P_3_P89") (pintype "bidirectional"))
    )
    (net (code "59") (name "/PD6") (class "Default")
      (node (ref "IC3") (pin "12") (pinfunction "PD6(INT6/AIN5/RTS)_12") (pintype "bidirectional"))
      (node (ref "U1") (pin "P87") (pinfunction "IO_L24N_3_P87") (pintype "bidirectional"))
    )
    (net (code "60") (name "/PROM_DO") (class "Default")
      (node (ref "IC1") (pin "1") (pinfunction "DO_1") (pintype "bidirectional"))
      (node (ref "U1") (pin "P65") (pinfunction "IO_L27N_4DIND0_P65") (pintype "bidirectional"))
    )
    (net (code "61") (name "/PROM_INITB") (class "Default")
      (node (ref "IC1") (pin "8") (pinfunction "OE/RESET_8") (pintype "bidirectional"))
      (node (ref "U1") (pin "P58") (pinfunction "IO_L31N_4INIT_B_P58") (pintype "bidirectional"))
    )
    (net (code "62") (name "/PS2CLK") (class "Default")
      (node (ref "R4") (pin "1") (pinfunction "1_1") (pintype "passive"))
      (node (ref "R47") (pin "2") (pinfunction "2_2") (pintype "passive"))
      (node (ref "T1") (pin "2") (pinfunction "S_2") (pintype "passive"))
      (node (ref "U1") (pin "P46") (pinfunction "IO_L28P_5D7_P46") (pintype "bidirectional"))
    )
    (net (code "63") (name "/PS2DAT") (class "Default")
      (node (ref "R51") (pin "2") (pinfunction "2_2") (pintype "passive"))
      (node (ref "R6") (pin "1") (pinfunction "1_1") (pintype "passive"))
      (node (ref "T3") (pin "2") (pinfunction "S_2") (pintype "passive"))
      (node (ref "U1") (pin "P44") (pinfunction "IOVREF_5_P44") (pintype "bidirectional"))
    )
    (net (code "64") (name "/R0") (class "Default")
      (node (ref "R10") (pin "1") (pinfunction "1_1") (pintype "passive"))
      (node (ref "U1") (pin "P55") (pinfunction "IO_L32P_4GCLK0_P55") (pintype "bidirectional"))
    )
    (net (code "65") (name "/R1") (class "Default")
      (node (ref "R9") (pin "1") (pinfunction "1_1") (pintype "passive"))
      (node (ref "U1") (pin "P53") (pinfunction "IO_L32N_5GCLK3_P53") (pintype "bidirectional"))
    )
    (net (code "66") (name "/RESET") (class "Default")
      (node (ref "R52") (pin "2") (pinfunction "2_2") (pintype "passive"))
      (node (ref "RESET_SW") (pin "1") (pinfunction "1_1") (pintype "passive"))
    )
    (net (code "67") (name "/SCART_BLANKING") (class "Default")
      (node (ref "R50") (pin "1") (pinfunction "1_1") (pintype "passive"))
      (node (ref "X1") (pin "16") (pinfunction "16_16") (pintype "passive"))
    )
    (net (code "68") (name "/SCART_BLUE") (class "Default")
      (node (ref "R31") (pin "1") (pinfunction "1_1") (pintype "passive"))
      (node (ref "R32") (pin "1") (pinfunction "1_1") (pintype "passive"))
      (node (ref "R33") (pin "1") (pinfunction "1_1") (pintype "passive"))
      (node (ref "X1") (pin "7") (pinfunction "7_7") (pintype "passive"))
    )
    (net (code "69") (name "/SCART_COMP") (class "Default")
      (node (ref "R13") (pin "1") (pinfunction "1_1") (pintype "passive"))
      (node (ref "R14") (pin "1") (pinfunction "1_1") (pintype "passive"))
      (node (ref "X1") (pin "19") (pinfunction "19_19") (pintype "passive"))
    )
    (net (code "70") (name "/SCART_GREEN") (class "Default")
      (node (ref "R26") (pin "1") (pinfunction "1_1") (pintype "passive"))
      (node (ref "R27") (pin "1") (pinfunction "1_1") (pintype "passive"))
      (node (ref "R28") (pin "1") (pinfunction "1_1") (pintype "passive"))
      (node (ref "X1") (pin "11") (pinfunction "11_11") (pintype "passive"))
    )
    (net (code "71") (name "/SCART_LEFT") (class "Default")
      (node (ref "C3") (pin "2") (pinfunction "2_2") (pintype "passive"))
      (node (ref "X1") (pin "3") (pinfunction "3_3") (pintype "passive"))
    )
    (net (code "72") (name "/SCART_MODE") (class "Default")
      (node (ref "X1") (pin "8") (pinfunction "8_8") (pintype "passive"))
    )
    (net (code "73") (name "/SCART_RED") (class "Default")
      (node (ref "R15") (pin "1") (pinfunction "1_1") (pintype "passive"))
      (node (ref "R16") (pin "1") (pinfunction "1_1") (pintype "passive"))
      (node (ref "R20") (pin "1") (pinfunction "1_1") (pintype "passive"))
      (node (ref "X1") (pin "15") (pinfunction "15_15") (pintype "passive"))
    )
    (net (code "74") (name "/SCART_RIGHT") (class "Default")
      (node (ref "C4") (pin "2") (pinfunction "2_2") (pintype "passive"))
      (node (ref "X1") (pin "1") (pinfunction "1_1") (pintype "passive"))
    )
    (net (code "75") (name "/SD_CLK") (class "Default")
      (node (ref "U$3") (pin "5") (pinfunction "SCLK_5") (pintype "input"))
      (node (ref "U1") (pin "P41") (pinfunction "IO_L01N_5RDWR_B_P41") (pintype "bidirectional"))
    )
    (net (code "76") (name "/SD_CS") (class "Default")
      (node (ref "U$3") (pin "1") (pinfunction "CS_1") (pintype "input"))
      (node (ref "U1") (pin "P140") (pinfunction "IO_L01P_0VRN_0_P140") (pintype "bidirectional"))
    )
    (net (code "77") (name "/SD_DI") (class "Default")
      (node (ref "U$3") (pin "2") (pinfunction "DATA_IN_2") (pintype "input"))
      (node (ref "U1") (pin "P141") (pinfunction "IO_L01N_0VRP_0_P141") (pintype "bidirectional"))
    )
    (net (code "78") (name "/SD_DO") (class "Default")
      (node (ref "U$3") (pin "7") (pinfunction "DATA_OUT_7") (pintype "output"))
      (node (ref "U1") (pin "P40") (pinfunction "IO_L01P_5CS_B_P40") (pintype "bidirectional"))
    )
    (net (code "79") (name "/SPI_MISO") (class "Default")
      (node (ref "IC3") (pin "17") (pinfunction "PB3(PDO/MISO/PCINT3)_17") (pintype "bidirectional"))
      (node (ref "SV2") (pin "4") (pinfunction "4_4") (pintype "passive"))
    )
    (net (code "80") (name "/SPI_MOSI") (class "Default")
      (node (ref "IC3") (pin "16") (pinfunction "PB2(PDI/MOSI/PCINT2)_16") (pintype "bidirectional"))
      (node (ref "SV2") (pin "2") (pinfunction "2_2") (pintype "passive"))
    )
    (net (code "81") (name "/SPI_SCLK") (class "Default")
      (node (ref "IC3") (pin "15") (pinfunction "PB1(SCK/PCINT1)_15") (pintype "bidirectional"))
      (node (ref "SV2") (pin "3") (pinfunction "3_3") (pintype "passive"))
    )
    (net (code "82") (name "/SPI_SEL") (class "Default")
      (node (ref "IC3") (pin "14") (pinfunction "PB0(SS/PCINT0)_14") (pintype "bidirectional"))
      (node (ref "SV2") (pin "1") (pinfunction "1_1") (pintype "passive"))
    )
    (net (code "83") (name "/TCK") (class "Default")
      (node (ref "IC1") (pin "6") (pinfunction "TCK_6") (pintype "bidirectional"))
      (node (ref "IC3") (pin "19") (pinfunction "PB5(PCINT5)_19") (pintype "bidirectional"))
      (node (ref "R2") (pin "2") (pinfunction "2_2") (pintype "passive"))
      (node (ref "SV4") (pin "7") (pinfunction "7_7") (pintype "passive"))
    )
    (net (code "84") (name "/TDI_FPGA") (class "Default")
      (node (ref "IC3") (pin "21") (pinfunction "PB7(OC0A/OC1C/PCINT7)_21") (pintype "bidirectional"))
      (node (ref "R1") (pin "2") (pinfunction "2_2") (pintype "passive"))
      (node (ref "SV4") (pin "5") (pinfunction "5_5") (pintype "passive"))
    )
    (net (code "85") (name "/TDO_EXP") (class "Default")
      (node (ref "IC3") (pin "23") (pinfunction "PC6(OC1A/PCINT8)_23") (pintype "bidirectional"))
      (node (ref "SV4") (pin "6") (pinfunction "6_6") (pintype "passive"))
    )
    (net (code "86") (name "/TDO_PROM") (class "Default")
      (node (ref "IC1") (pin "17") (pinfunction "TDO_17") (pintype "bidirectional"))
      (node (ref "IC3") (pin "20") (pinfunction "PB6(PCINT6)_20") (pintype "bidirectional"))
      (node (ref "SV4") (pin "8") (pinfunction "8_8") (pintype "passive"))
    )
    (net (code "87") (name "/TMS") (class "Default")
      (node (ref "IC1") (pin "5") (pinfunction "TMS_5") (pintype "bidirectional"))
      (node (ref "IC3") (pin "18") (pinfunction "PB4(T1/PCINT4)_18") (pintype "bidirectional"))
      (node (ref "R3") (pin "2") (pinfunction "2_2") (pintype "passive"))
      (node (ref "SV4") (pin "10") (pinfunction "10_10") (pintype "passive"))
    )
    (net (code "88") (name "/VCC") (class "Default")
      (node (ref "C10") (pin "1") (pinfunction "1_1") (pintype "passive"))
      (node (ref "C11") (pin "1") (pinfunction "1_1") (pintype "passive"))
      (node (ref "C12") (pin "1") (pinfunction "1_1") (pintype "passive"))
      (node (ref "C13") (pin "1") (pinfunction "1_1") (pintype "passive"))
      (node (ref "C14") (pin "1") (pinfunction "1_1") (pintype "passive"))
      (node (ref "C15") (pin "1") (pinfunction "1_1") (pintype "passive"))
      (node (ref "C16") (pin "1") (pinfunction "1_1") (pintype "passive"))
      (node (ref "C17") (pin "1") (pinfunction "1_1") (pintype "passive"))
      (node (ref "C26") (pin "1") (pinfunction "1_1") (pintype "passive"))
      (node (ref "C27") (pin "1") (pinfunction "1_1") (pintype "passive"))
      (node (ref "C28") (pin "1") (pinfunction "1_1") (pintype "passive"))
      (node (ref "C29") (pin "1") (pinfunction "1_1") (pintype "passive"))
      (node (ref "C30") (pin "1") (pinfunction "1_1") (pintype "passive"))
      (node (ref "C31") (pin "1") (pinfunction "1_1") (pintype "passive"))
      (node (ref "C32") (pin "1") (pinfunction "1_1") (pintype "passive"))
      (node (ref "C34") (pin "1") (pinfunction "1_1") (pintype "passive"))
      (node (ref "C39") (pin "+") (pinfunction "+_+") (pintype "passive"))
      (node (ref "C6") (pin "1") (pinfunction "1_1") (pintype "passive"))
      (node (ref "C7") (pin "1") (pinfunction "1_1") (pintype "passive"))
      (node (ref "C8") (pin "1") (pinfunction "1_1") (pintype "passive"))
      (node (ref "C9") (pin "1") (pinfunction "1_1") (pintype "passive"))
      (node (ref "IC1") (pin "18") (pinfunction "VCCINT_18") (pintype "bidirectional"))
      (node (ref "IC1") (pin "19") (pinfunction "VCCO_19") (pintype "bidirectional"))
      (node (ref "IC1") (pin "20") (pinfunction "VCCJ_20") (pintype "bidirectional"))
      (node (ref "IC2") (pin "8") (pinfunction "VCC_8") (pintype "power_in"))
      (node (ref "IC3") (pin "31") (pinfunction "UVCC_31") (pintype "bidirectional"))
      (node (ref "IC3") (pin "32") (pinfunction "AVCC_32") (pintype "bidirectional"))
      (node (ref "IC3") (pin "4") (pinfunction "VCC_4") (pintype "bidirectional"))
      (node (ref "JP1") (pin "2") (pinfunction "2_2") (pintype "passive"))
      (node (ref "Q5") (pin "3") (pinfunction "C_3") (pintype "passive"))
      (node (ref "Q6") (pin "3") (pinfunction "C_3") (pintype "passive"))
      (node (ref "Q7") (pin "3") (pinfunction "C_3") (pintype "passive"))
      (node (ref "Q8") (pin "3") (pinfunction "C_3") (pintype "passive"))
      (node (ref "R22") (pin "1") (pinfunction "1_1") (pintype "passive"))
      (node (ref "R35") (pin "2") (pinfunction "2_2") (pintype "passive"))
      (node (ref "R36") (pin "2") (pinfunction "2_2") (pintype "passive"))
      (node (ref "R37") (pin "2") (pinfunction "2_2") (pintype "passive"))
      (node (ref "R38") (pin "2") (pinfunction "2_2") (pintype "passive"))
      (node (ref "R39") (pin "2") (pinfunction "2_2") (pintype "passive"))
      (node (ref "R4") (pin "2") (pinfunction "2_2") (pintype "passive"))
      (node (ref "R40") (pin "1") (pinfunction "1_1") (pintype "passive"))
      (node (ref "R41") (pin "1") (pinfunction "1_1") (pintype "passive"))
      (node (ref "R42") (pin "1") (pinfunction "1_1") (pintype "passive"))
      (node (ref "R43") (pin "1") (pinfunction "1_1") (pintype "passive"))
      (node (ref "R44") (pin "1") (pinfunction "1_1") (pintype "passive"))
      (node (ref "R45") (pin "1") (pinfunction "1_1") (pintype "passive"))
      (node (ref "R46") (pin "2") (pinfunction "2_2") (pintype "passive"))
      (node (ref "R52") (pin "1") (pinfunction "1_1") (pintype "passive"))
      (node (ref "R55") (pin "1") (pinfunction "1_1") (pintype "passive"))
      (node (ref "R56") (pin "1") (pinfunction "1_1") (pintype "passive"))
      (node (ref "R6") (pin "2") (pinfunction "2_2") (pintype "passive"))
      (node (ref "SV2") (pin "5") (pinfunction "5_5") (pintype "passive"))
      (node (ref "SV3") (pin "1") (pinfunction "1_1") (pintype "passive"))
      (node (ref "SV4") (pin "19") (pinfunction "19_19") (pintype "passive"))
      (node (ref "SV4") (pin "20") (pinfunction "20_20") (pintype "passive"))
      (node (ref "SV4") (pin "9") (pinfunction "9_9") (pintype "passive"))
      (node (ref "SV5") (pin "3") (pinfunction "3_3") (pintype "passive"))
      (node (ref "SV5") (pin "4") (pinfunction "4_4") (pintype "passive"))
      (node (ref "T1") (pin "3") (pinfunction "G_3") (pintype "passive"))
      (node (ref "T2") (pin "3") (pinfunction "C_3") (pintype "passive"))
      (node (ref "T3") (pin "3") (pinfunction "G_3") (pintype "passive"))
      (node (ref "U$2") (pin "VDD") (pinfunction "VDD_VDD") (pintype "power_in"))
      (node (ref "U$3") (pin "4") (pinfunction "VDD_4") (pintype "power_in"))
      (node (ref "U$4") (pin "4") (pinfunction "VOUT1_4") (pintype "bidirectional"))
      (node (ref "U$5") (pin "2") (pinfunction "VOUT1_2") (pintype "output"))
      (node (ref "U$5") (pin "3") (pinfunction "VOUT2_3") (pintype "output"))
      (node (ref "U$5") (pin "6") (pinfunction "VOUT3_6") (pintype "output"))
      (node (ref "U$5") (pin "7") (pinfunction "VOUT4_7") (pintype "output"))
      (node (ref "U$6") (pin "P8") (pinfunction "VCC_P8") (pintype "bidirectional"))
      (node (ref "U1") (pin "P106") (pinfunction "VCCO_RIGHT2_P106") (pintype "passive"))
      (node (ref "U1") (pin "P115") (pinfunction "VCCO_TOP0_P115") (pintype "passive"))
      (node (ref "U1") (pin "P126") (pinfunction "VCCO_TOP1_P126") (pintype "passive"))
      (node (ref "U1") (pin "P138") (pinfunction "VCCO_TOP2_P138") (pintype "passive"))
      (node (ref "U1") (pin "P19") (pinfunction "VCCO_LEFT1_P19") (pintype "passive"))
      (node (ref "U1") (pin "P3") (pinfunction "VCCO_LEFT0_P3") (pintype "passive"))
      (node (ref "U1") (pin "P34") (pinfunction "VCCO_LEFT2_P34") (pintype "passive"))
      (node (ref "U1") (pin "P43") (pinfunction "VCCO_BOTTOM0_P43") (pintype "passive"))
      (node (ref "U1") (pin "P54") (pinfunction "VCCO_BOTTOM1_P54") (pintype "passive"))
      (node (ref "U1") (pin "P66") (pinfunction "VCCO_BOTTOM2_P66") (pintype "passive"))
      (node (ref "U1") (pin "P75") (pinfunction "VCCO_RIGHT0_P75") (pintype "passive"))
      (node (ref "U1") (pin "P91") (pinfunction "VCCO_RIGHT1_P91") (pintype "passive"))
    )
    (net (code "89") (name "/VCC5") (class "Default")
      (node (ref "C33") (pin "+") (pinfunction "+_+") (pintype "passive"))
      (node (ref "PWR_HDR") (pin "2") (pinfunction "2_2") (pintype "passive"))
      (node (ref "R5") (pin "2") (pinfunction "2_2") (pintype "passive"))
      (node (ref "R7") (pin "2") (pinfunction "2_2") (pintype "passive"))
      (node (ref "REG1.2") (pin "3") (pinfunction "VCC_3") (pintype "bidirectional"))
      (node (ref "REG2.5") (pin "3") (pinfunction "VCC_3") (pintype "bidirectional"))
      (node (ref "SV5") (pin "10") (pinfunction "10_10") (pintype "passive"))
      (node (ref "SV5") (pin "9") (pinfunction "9_9") (pintype "passive"))
      (node (ref "U$4") (pin "3") (pinfunction "VCC_3") (pintype "bidirectional"))
      (node (ref "U$5") (pin "4") (pinfunction "VCC_4") (pintype "bidirectional"))
      (node (ref "X3") (pin "5") (pinfunction "5_5") (pintype "passive"))
      (node (ref "X7") (pin "2") (pinfunction "2_2") (pintype "power_in"))
    )
    (net (code "90") (name "/VCCAUX") (class "Default")
      (node (ref "C18") (pin "1") (pinfunction "1_1") (pintype "passive"))
      (node (ref "C19") (pin "1") (pinfunction "1_1") (pintype "passive"))
      (node (ref "C20") (pin "1") (pinfunction "1_1") (pintype "passive"))
      (node (ref "C21") (pin "1") (pinfunction "1_1") (pintype "passive"))
      (node (ref "C40") (pin "+") (pinfunction "+_+") (pintype "passive"))
      (node (ref "R50") (pin "2") (pinfunction "2_2") (pintype "passive"))
      (node (ref "REG2.5") (pin "4") (pinfunction "VOUT1_4") (pintype "bidirectional"))
      (node (ref "SV5") (pin "2") (pinfunction "2_2") (pintype "passive"))
      (node (ref "U1") (pin "P120") (pinfunction "VCCAUX2_P120") (pintype "passive"))
      (node (ref "U1") (pin "P134") (pinfunction "VCCAUX3_P134") (pintype "passive"))
      (node (ref "U1") (pin "P48") (pinfunction "VCCAUX0_P48") (pintype "passive"))
      (node (ref "U1") (pin "P62") (pinfunction "VCCAUX1_P62") (pintype "passive"))
    )
    (net (code "91") (name "/VCCINT") (class "Default")
      (node (ref "C22") (pin "1") (pinfunction "1_1") (pintype "passive"))
      (node (ref "C23") (pin "1") (pinfunction "1_1") (pintype "passive"))
      (node (ref "C24") (pin "1") (pinfunction "1_1") (pintype "passive"))
      (node (ref "C25") (pin "1") (pinfunction "1_1") (pintype "passive"))
      (node (ref "C42") (pin "+") (pinfunction "+_+") (pintype "passive"))
      (node (ref "REG1.2") (pin "4") (pinfunction "VOUT1_4") (pintype "bidirectional"))
      (node (ref "SV5") (pin "1") (pinfunction "1_1") (pintype "passive"))
      (node (ref "U1") (pin "P121") (pinfunction "VCCINT2_P121") (pintype "passive"))
      (node (ref "U1") (pin "P133") (pinfunction "VCCINT3_P133") (pintype "passive"))
      (node (ref "U1") (pin "P49") (pinfunction "VCCINT0_P49") (pintype "passive"))
      (node (ref "U1") (pin "P61") (pinfunction "VCCINT1_P61") (pintype "passive"))
    )
    (net (code "92") (name "/VCC_B3") (class "Default")
      (node (ref "R11") (pin "2") (pinfunction "2_2") (pintype "passive"))
    )
    (net (code "94") (name "/XAXAXA") (class "Default")
      (node (ref "SV4") (pin "12") (pinfunction "12_12") (pintype "passive"))
    )
    (net (code "96") (name "GND") (class "Default")
      (node (ref "C1") (pin "1") (pinfunction "1_1") (pintype "passive"))
      (node (ref "C10") (pin "2") (pinfunction "2_2") (pintype "passive"))
      (node (ref "C11") (pin "2") (pinfunction "2_2") (pintype "passive"))
      (node (ref "C12") (pin "2") (pinfunction "2_2") (pintype "passive"))
      (node (ref "C13") (pin "2") (pinfunction "2_2") (pintype "passive"))
      (node (ref "C14") (pin "2") (pinfunction "2_2") (pintype "passive"))
      (node (ref "C15") (pin "2") (pinfunction "2_2") (pintype "passive"))
      (node (ref "C16") (pin "2") (pinfunction "2_2") (pintype "passive"))
      (node (ref "C17") (pin "2") (pinfunction "2_2") (pintype "passive"))
      (node (ref "C18") (pin "2") (pinfunction "2_2") (pintype "passive"))
      (node (ref "C19") (pin "2") (pinfunction "2_2") (pintype "passive"))
      (node (ref "C20") (pin "2") (pinfunction "2_2") (pintype "passive"))
      (node (ref "C21") (pin "2") (pinfunction "2_2") (pintype "passive"))
      (node (ref "C22") (pin "2") (pinfunction "2_2") (pintype "passive"))
      (node (ref "C23") (pin "2") (pinfunction "2_2") (pintype "passive"))
      (node (ref "C24") (pin "2") (pinfunction "2_2") (pintype "passive"))
      (node (ref "C25") (pin "2") (pinfunction "2_2") (pintype "passive"))
      (node (ref "C26") (pin "2") (pinfunction "2_2") (pintype "passive"))
      (node (ref "C27") (pin "2") (pinfunction "2_2") (pintype "passive"))
      (node (ref "C28") (pin "2") (pinfunction "2_2") (pintype "passive"))
      (node (ref "C29") (pin "2") (pinfunction "2_2") (pintype "passive"))
      (node (ref "C30") (pin "2") (pinfunction "2_2") (pintype "passive"))
      (node (ref "C31") (pin "2") (pinfunction "2_2") (pintype "passive"))
      (node (ref "C32") (pin "2") (pinfunction "2_2") (pintype "passive"))
      (node (ref "C33") (pin "-") (pinfunction "-_-") (pintype "passive"))
      (node (ref "C34") (pin "2") (pinfunction "2_2") (pintype "passive"))
      (node (ref "C37") (pin "1") (pinfunction "1_1") (pintype "passive"))
      (node (ref "C38") (pin "1") (pinfunction "1_1") (pintype "passive"))
      (node (ref "C39") (pin "-") (pinfunction "-_-") (pintype "passive"))
      (node (ref "C40") (pin "-") (pinfunction "-_-") (pintype "passive"))
      (node (ref "C41") (pin "2") (pinfunction "2_2") (pintype "passive"))
      (node (ref "C42") (pin "-") (pinfunction "-_-") (pintype "passive"))
      (node (ref "C5") (pin "1") (pinfunction "1_1") (pintype "passive"))
      (node (ref "C6") (pin "2") (pinfunction "2_2") (pintype "passive"))
      (node (ref "C7") (pin "2") (pinfunction "2_2") (pintype "passive"))
      (node (ref "C8") (pin "2") (pinfunction "2_2") (pintype "passive"))
      (node (ref "C9") (pin "2") (pinfunction "2_2") (pintype "passive"))
      (node (ref "IC1") (pin "11") (pinfunction "GND_11") (pintype "bidirectional"))
      (node (ref "IC2") (pin "4") (pinfunction "GND_4") (pintype "power_in"))
      (node (ref "IC3") (pin "3") (pinfunction "GND_3") (pintype "bidirectional"))
      (node (ref "JP1") (pin "1") (pinfunction "1_1") (pintype "passive"))
      (node (ref "PWR_HDR") (pin "1") (pinfunction "1_1") (pintype "passive"))
      (node (ref "R12") (pin "1") (pinfunction "1_1") (pintype "passive"))
      (node (ref "R17") (pin "1") (pinfunction "1_1") (pintype "passive"))
      (node (ref "R19") (pin "1") (pinfunction "1_1") (pintype "passive"))
      (node (ref "R21") (pin "1") (pinfunction "1_1") (pintype "passive"))
      (node (ref "REG1.2") (pin "1") (pinfunction "GND_1") (pintype "bidirectional"))
      (node (ref "REG2.5") (pin "1") (pinfunction "GND_1") (pintype "bidirectional"))
      (node (ref "RESET_SW") (pin "2") (pinfunction "2_2") (pintype "passive"))
      (node (ref "SV2") (pin "6") (pinfunction "6_6") (pintype "passive"))
      (node (ref "SV3") (pin "2") (pinfunction "2_2") (pintype "passive"))
      (node (ref "SV4") (pin "11") (pinfunction "11_11") (pintype "passive"))
      (node (ref "SV4") (pin "3") (pinfunction "3_3") (pintype "passive"))
      (node (ref "SV4") (pin "4") (pinfunction "4_4") (pintype "passive"))
      (node (ref "SV5") (pin "7") (pinfunction "7_7") (pintype "passive"))
      (node (ref "U$1") (pin "GND") (pinfunction "GND_GND") (pintype "bidirectional"))
      (node (ref "U$2") (pin "GND") (pinfunction "GND_GND") (pintype "power_in"))
      (node (ref "U$3") (pin "3") (pinfunction "VSS1_3") (pintype "power_in"))
      (node (ref "U$3") (pin "6") (pinfunction "VSS2_6") (pintype "power_in"))
      (node (ref "U$3") (pin "MT1") (pinfunction "COMMON_SW_MT1") (pintype "passive"))
      (node (ref "U$3") (pin "MT3") (pinfunction "GND_MT3") (pintype "power_in"))
      (node (ref "U$4") (pin "1") (pinfunction "GND_1") (pintype "bidirectional"))
      (node (ref "U$5") (pin "1") (pinfunction "GND_1") (pintype "bidirectional"))
      (node (ref "U$6") (pin "P24") (pinfunction "VSS_P24") (pintype "bidirectional"))
      (node (ref "U$6") (pin "P30") (pinfunction "CE_P30") (pintype "bidirectional"))
      (node (ref "U$7") (pin "GND") (pinfunction "GND_GND") (pintype "bidirectional"))
      (node (ref "U$8") (pin "GND") (pinfunction "GND_GND") (pintype "bidirectional"))
      (node (ref "U$9") (pin "GND") (pinfunction "GND_GND") (pintype "bidirectional"))
      (node (ref "U1") (pin "P101") (pinfunction "GND11_P101") (pintype "passive"))
      (node (ref "U1") (pin "P114") (pinfunction "GND12_P114") (pintype "passive"))
      (node (ref "U1") (pin "P117") (pinfunction "GND13_P117") (pintype "passive"))
      (node (ref "U1") (pin "P136") (pinfunction "GND14_P136") (pintype "passive"))
      (node (ref "U1") (pin "P139") (pinfunction "GND15_P139") (pintype "passive"))
      (node (ref "U1") (pin "P16") (pinfunction "GND1_P16") (pintype "passive"))
      (node (ref "U1") (pin "P22") (pinfunction "GND2_P22") (pintype "passive"))
      (node (ref "U1") (pin "P29") (pinfunction "GND3_P29") (pintype "passive"))
      (node (ref "U1") (pin "P37") (pinfunction "M1_P37") (pintype "bidirectional"))
      (node (ref "U1") (pin "P38") (pinfunction "M0_P38") (pintype "bidirectional"))
      (node (ref "U1") (pin "P39") (pinfunction "M2_P39") (pintype "bidirectional"))
      (node (ref "U1") (pin "P42") (pinfunction "GND4_P42") (pintype "passive"))
      (node (ref "U1") (pin "P45") (pinfunction "GND5_P45") (pintype "passive"))
      (node (ref "U1") (pin "P64") (pinfunction "GND6_P64") (pintype "passive"))
      (node (ref "U1") (pin "P67") (pinfunction "GND7_P67") (pintype "passive"))
      (node (ref "U1") (pin "P81") (pinfunction "GND8_P81") (pintype "passive"))
      (node (ref "U1") (pin "P88") (pinfunction "GND9_P88") (pintype "passive"))
      (node (ref "U1") (pin "P9") (pinfunction "GND0_P9") (pintype "passive"))
      (node (ref "U1") (pin "P94") (pinfunction "GND10_P94") (pintype "passive"))
      (node (ref "X1") (pin "13") (pinfunction "13_13") (pintype "passive"))
      (node (ref "X1") (pin "14") (pinfunction "14_14") (pintype "passive"))
      (node (ref "X1") (pin "17") (pinfunction "17_17") (pintype "passive"))
      (node (ref "X1") (pin "18") (pinfunction "18_18") (pintype "passive"))
      (node (ref "X1") (pin "21") (pinfunction "21_21") (pintype "passive"))
      (node (ref "X1") (pin "4") (pinfunction "4_4") (pintype "passive"))
      (node (ref "X1") (pin "5") (pinfunction "5_5") (pintype "passive"))
      (node (ref "X1") (pin "9") (pinfunction "9_9") (pintype "passive"))
      (node (ref "X3") (pin "3") (pinfunction "3_3") (pintype "passive"))
      (node (ref "X3") (pin "SH1") (pinfunction "PE1_SH1") (pintype "power_in"))
      (node (ref "X3") (pin "SH2") (pinfunction "PE2_SH2") (pintype "power_in"))
      (node (ref "X3") (pin "SH3") (pinfunction "PE3_SH3") (pintype "power_in"))
      (node (ref "X4") (pin "8") (pinfunction "F_8") (pintype "passive"))
      (node (ref "X4") (pin "G1") (pinfunction "G1_G1") (pintype "passive"))
      (node (ref "X5") (pin "8") (pinfunction "F_8") (pintype "passive"))
      (node (ref "X5") (pin "G1") (pinfunction "G1_G1") (pintype "passive"))
      (node (ref "X7") (pin "3") (pinfunction "3_3") (pintype "power_in"))
      (node (ref "X8") (pin "1") (pinfunction "1_1") (pintype "passive"))
    )
    (net (code "97") (name "Net-(C1-Pad2)") (class "Default")
      (node (ref "C1") (pin "2") (pinfunction "2_2") (pintype "passive"))
      (node (ref "R23") (pin "2") (pinfunction "2_2") (pintype "passive"))
      (node (ref "R48") (pin "1") (pinfunction "1_1") (pintype "passive"))
    )
    (net (code "98") (name "Net-(C2-Pad1)") (class "Default")
      (node (ref "C2") (pin "1") (pinfunction "1_1") (pintype "passive"))
      (node (ref "R17") (pin "2") (pinfunction "2_2") (pintype "passive"))
      (node (ref "X8") (pin "2") (pinfunction "2_2") (pintype "passive"))
      (node (ref "X8") (pin "3") (pinfunction "3_3") (pintype "passive"))
      (node (ref "X8") (pin "4") (pinfunction "4_4") (pintype "passive"))
      (node (ref "X8") (pin "5") (pinfunction "5_5") (pintype "passive"))
    )
    (net (code "99") (name "Net-(C3-Pad1)") (class "Default")
      (node (ref "C3") (pin "1") (pinfunction "1_1") (pintype "passive"))
      (node (ref "R48") (pin "2") (pinfunction "2_2") (pintype "passive"))
    )
    (net (code "100") (name "Net-(C4-Pad1)") (class "Default")
      (node (ref "C4") (pin "1") (pinfunction "1_1") (pintype "passive"))
      (node (ref "R49") (pin "2") (pinfunction "2_2") (pintype "passive"))
    )
    (net (code "101") (name "Net-(C5-Pad2)") (class "Default")
      (node (ref "C5") (pin "2") (pinfunction "2_2") (pintype "passive"))
      (node (ref "R34") (pin "2") (pinfunction "2_2") (pintype "passive"))
      (node (ref "R49") (pin "1") (pinfunction "1_1") (pintype "passive"))
    )
    (net (code "102") (name "Net-(C38-Pad2)") (class "Default")
      (node (ref "C38") (pin "2") (pinfunction "2_2") (pintype "passive"))
      (node (ref "Q1") (pin "2") (pinfunction "2_2") (pintype "passive"))
      (node (ref "SJ1") (pin "1") (pinfunction "1_1") (pintype "passive"))
    )
    (net (code "103") (name "Net-(IC1-CLK)") (class "Default")
      (node (ref "IC1") (pin "3") (pinfunction "CLK_3") (pintype "bidirectional"))
      (node (ref "U1") (pin "P72") (pinfunction "CCLK_P72") (pintype "bidirectional"))
    )
    (net (code "104") (name "Net-(IC1-TDI)") (class "Default")
      (node (ref "IC1") (pin "4") (pinfunction "TDI_4") (pintype "bidirectional"))
      (node (ref "U1") (pin "P109") (pinfunction "TDO_P109") (pintype "bidirectional"))
    )
    (net (code "105") (name "Net-(IC1-{slash}CE)") (class "Default")
      (node (ref "IC1") (pin "10") (pinfunction "/CE_10") (pintype "bidirectional"))
      (node (ref "U1") (pin "P71") (pinfunction "DONE_P71") (pintype "bidirectional"))
    )
    (net (code "106") (name "Net-(IC1-{slash}CF)") (class "Default")
      (node (ref "IC1") (pin "7") (pinfunction "/CF_7") (pintype "bidirectional"))
      (node (ref "U1") (pin "P143") (pinfunction "PROG_B_P143") (pintype "bidirectional"))
    )
    (net (code "107") (name "Net-(IC3-D+)") (class "Default")
      (node (ref "IC3") (pin "29") (pinfunction "D+_29") (pintype "bidirectional"))
      (node (ref "R54") (pin "2") (pinfunction "2_2") (pintype "passive"))
    )
    (net (code "108") (name "Net-(IC3-D-)") (class "Default")
      (node (ref "IC3") (pin "30") (pinfunction "D-_30") (pintype "bidirectional"))
      (node (ref "R53") (pin "2") (pinfunction "2_2") (pintype "passive"))
    )
    (net (code "109") (name "Net-(IC3-UCAP)") (class "Default")
      (node (ref "C41") (pin "1") (pinfunction "1_1") (pintype "passive"))
      (node (ref "IC3") (pin "27") (pinfunction "UCAP_27") (pintype "bidirectional"))
    )
    (net (code "110") (name "Net-(IC3-UGND)") (class "Default")
      (node (ref "IC3") (pin "28") (pinfunction "UGND_28") (pintype "bidirectional"))
      (node (ref "X6") (pin "4") (pinfunction "4_4") (pintype "passive"))
    )
    (net (code "111") (name "Net-(IC3-XTAL1)") (class "Default")
      (node (ref "IC3") (pin "1") (pinfunction "XTAL1_1") (pintype "bidirectional"))
      (node (ref "SJ1") (pin "2") (pinfunction "2_2") (pintype "passive"))
    )
    (net (code "112") (name "Net-(IC3-XTAL2{slash}PC0)") (class "Default")
      (node (ref "C37") (pin "2") (pinfunction "2_2") (pintype "passive"))
      (node (ref "IC3") (pin "2") (pinfunction "XTAL2/PC0_2") (pintype "bidirectional"))
      (node (ref "Q1") (pin "1") (pinfunction "1_1") (pintype "passive"))
    )
    (net (code "113") (name "Net-(Q5-B)") (class "Default")
      (node (ref "Q5") (pin "1") (pinfunction "B_1") (pintype "passive"))
      (node (ref "R8") (pin "2") (pinfunction "2_2") (pintype "passive"))
    )
    (net (code "114") (name "Net-(Q5-E)") (class "Default")
      (node (ref "Q5") (pin "2") (pinfunction "E_2") (pintype "passive"))
      (node (ref "R13") (pin "2") (pinfunction "2_2") (pintype "passive"))
      (node (ref "R14") (pin "2") (pinfunction "2_2") (pintype "passive"))
    )
    (net (code "115") (name "Net-(Q6-B)") (class "Default")
      (node (ref "Q6") (pin "1") (pinfunction "B_1") (pintype "passive"))
      (node (ref "R10") (pin "2") (pinfunction "2_2") (pintype "passive"))
      (node (ref "R9") (pin "2") (pinfunction "2_2") (pintype "passive"))
    )
    (net (code "116") (name "Net-(Q6-E)") (class "Default")
      (node (ref "Q6") (pin "2") (pinfunction "E_2") (pintype "passive"))
      (node (ref "R15") (pin "2") (pinfunction "2_2") (pintype "passive"))
      (node (ref "R16") (pin "2") (pinfunction "2_2") (pintype "passive"))
      (node (ref "R20") (pin "2") (pinfunction "2_2") (pintype "passive"))
    )
    (net (code "117") (name "Net-(Q7-B)") (class "Default")
      (node (ref "Q7") (pin "1") (pinfunction "B_1") (pintype "passive"))
      (node (ref "R29") (pin "2") (pinfunction "2_2") (pintype "passive"))
      (node (ref "R30") (pin "2") (pinfunction "2_2") (pintype "passive"))
    )
    (net (code "118") (name "Net-(Q7-E)") (class "Default")
      (node (ref "Q7") (pin "2") (pinfunction "E_2") (pintype "passive"))
      (node (ref "R31") (pin "2") (pinfunction "2_2") (pintype "passive"))
      (node (ref "R32") (pin "2") (pinfunction "2_2") (pintype "passive"))
      (node (ref "R33") (pin "2") (pinfunction "2_2") (pintype "passive"))
    )
    (net (code "119") (name "Net-(Q8-B)") (class "Default")
      (node (ref "Q8") (pin "1") (pinfunction "B_1") (pintype "passive"))
      (node (ref "R24") (pin "2") (pinfunction "2_2") (pintype "passive"))
      (node (ref "R25") (pin "2") (pinfunction "2_2") (pintype "passive"))
    )
    (net (code "120") (name "Net-(Q8-E)") (class "Default")
      (node (ref "Q8") (pin "2") (pinfunction "E_2") (pintype "passive"))
      (node (ref "R26") (pin "2") (pinfunction "2_2") (pintype "passive"))
      (node (ref "R27") (pin "2") (pinfunction "2_2") (pintype "passive"))
      (node (ref "R28") (pin "2") (pinfunction "2_2") (pintype "passive"))
    )
    (net (code "121") (name "Net-(R18-Pad2)") (class "Default")
      (node (ref "R18") (pin "2") (pinfunction "2_2") (pintype "passive"))
      (node (ref "R22") (pin "2") (pinfunction "2_2") (pintype "passive"))
    )
    (net (code "122") (name "Net-(R53-Pad1)") (class "Default")
      (node (ref "R53") (pin "1") (pinfunction "1_1") (pintype "passive"))
      (node (ref "X6") (pin "2") (pinfunction "2_2") (pintype "passive"))
    )
    (net (code "123") (name "Net-(R54-Pad1)") (class "Default")
      (node (ref "R54") (pin "1") (pinfunction "1_1") (pintype "passive"))
      (node (ref "X6") (pin "3") (pinfunction "3_3") (pintype "passive"))
    )
    (net (code "124") (name "Net-(T2-B)") (class "Default")
      (node (ref "C2") (pin "2") (pinfunction "2_2") (pintype "passive"))
      (node (ref "R18") (pin "1") (pinfunction "1_1") (pintype "passive"))
      (node (ref "R19") (pin "2") (pinfunction "2_2") (pintype "passive"))
      (node (ref "T2") (pin "1") (pinfunction "B_1") (pintype "passive"))
    )
    (net (code "125") (name "Net-(U$6-A0)") (class "Default")
      (node (ref "U$6") (pin "P20") (pinfunction "A0_P20") (pintype "bidirectional"))
      (node (ref "U1") (pin "P24") (pinfunction "IO_L24N_6VREF_6_P24") (pintype "bidirectional"))
    )
    (net (code "126") (name "Net-(U$6-A1)") (class "Default")
      (node (ref "U$6") (pin "P19") (pinfunction "A1_P19") (pintype "bidirectional"))
      (node (ref "U1") (pin "P23") (pinfunction "IO_L24P_6_P23") (pintype "bidirectional"))
    )
    (net (code "127") (name "Net-(U$6-A2)") (class "Default")
      (node (ref "U$6") (pin "P18") (pinfunction "A2_P18") (pintype "bidirectional"))
      (node (ref "U1") (pin "P21") (pinfunction "IO_L40N_6_P21") (pintype "bidirectional"))
    )
    (net (code "128") (name "Net-(U$6-A3)") (class "Default")
      (node (ref "U$6") (pin "P17") (pinfunction "A3_P17") (pintype "bidirectional"))
      (node (ref "U1") (pin "P20") (pinfunction "IO_L40P_6VREF_6_P20") (pintype "bidirectional"))
    )
    (net (code "129") (name "Net-(U$6-A4)") (class "Default")
      (node (ref "U$6") (pin "P16") (pinfunction "A4_P16") (pintype "bidirectional"))
      (node (ref "U1") (pin "P18") (pinfunction "IO_L40N_7VREF_7_P18") (pintype "bidirectional"))
    )
    (net (code "130") (name "Net-(U$6-A5)") (class "Default")
      (node (ref "U$6") (pin "P15") (pinfunction "A5_P15") (pintype "bidirectional"))
      (node (ref "U1") (pin "P17") (pinfunction "IO_L40P_7_P17") (pintype "bidirectional"))
    )
    (net (code "131") (name "Net-(U$6-A6)") (class "Default")
      (node (ref "U$6") (pin "P14") (pinfunction "A6_P14") (pintype "bidirectional"))
      (node (ref "U1") (pin "P15") (pinfunction "IO_L24N_7_P15") (pintype "bidirectional"))
    )
    (net (code "132") (name "Net-(U$6-A7)") (class "Default")
      (node (ref "U$6") (pin "P13") (pinfunction "A7_P13") (pintype "bidirectional"))
      (node (ref "U1") (pin "P14") (pinfunction "IO_L24P_7_P14") (pintype "bidirectional"))
    )
    (net (code "133") (name "Net-(U$6-A8)") (class "Default")
      (node (ref "U$6") (pin "P3") (pinfunction "A8_P3") (pintype "bidirectional"))
      (node (ref "U1") (pin "P4") (pinfunction "IOVREF_7_P4") (pintype "bidirectional"))
    )
    (net (code "134") (name "Net-(U$6-A9)") (class "Default")
      (node (ref "U$6") (pin "P2") (pinfunction "A9_P2") (pintype "bidirectional"))
      (node (ref "U1") (pin "P2") (pinfunction "IO_L01N_7VRP_7_P2") (pintype "bidirectional"))
    )
    (net (code "135") (name "Net-(U$6-A10)") (class "Default")
      (node (ref "U$6") (pin "P31") (pinfunction "A10_P31") (pintype "bidirectional"))
      (node (ref "U1") (pin "P35") (pinfunction "IO_L01P_6VRN_6_P35") (pintype "bidirectional"))
    )
    (net (code "136") (name "Net-(U$6-A11)") (class "Default")
      (node (ref "U$6") (pin "P1") (pinfunction "A11_P1") (pintype "bidirectional"))
      (node (ref "U1") (pin "P1") (pinfunction "IO_L01P_7VRN_7_P1") (pintype "bidirectional"))
    )
    (net (code "137") (name "Net-(U$6-A12)") (class "Default")
      (node (ref "U$6") (pin "P12") (pinfunction "A12_P12") (pintype "bidirectional"))
      (node (ref "U1") (pin "P13") (pinfunction "IO_L23N_7_P13") (pintype "bidirectional"))
    )
    (net (code "138") (name "Net-(U$6-A13)") (class "Default")
      (node (ref "U$6") (pin "P4") (pinfunction "A13_P4") (pintype "bidirectional"))
      (node (ref "U1") (pin "P5") (pinfunction "IO_L20P_7_P5") (pintype "bidirectional"))
    )
    (net (code "139") (name "Net-(U$6-A14)") (class "Default")
      (node (ref "U$6") (pin "P11") (pinfunction "A14_P11") (pintype "bidirectional"))
      (node (ref "U1") (pin "P12") (pinfunction "IO_L23P_7_P12") (pintype "bidirectional"))
    )
    (net (code "140") (name "Net-(U$6-A15)") (class "Default")
      (node (ref "U$6") (pin "P7") (pinfunction "A15_P7") (pintype "bidirectional"))
      (node (ref "U1") (pin "P8") (pinfunction "IO_L21N_7_P8") (pintype "bidirectional"))
    )
    (net (code "141") (name "Net-(U$6-A16)") (class "Default")
      (node (ref "U$6") (pin "P10") (pinfunction "A16_P10") (pintype "bidirectional"))
      (node (ref "U1") (pin "P11") (pinfunction "IO_L22N_7_P11") (pintype "bidirectional"))
    )
    (net (code "142") (name "Net-(U$6-A17)") (class "Default")
      (node (ref "U$6") (pin "P6") (pinfunction "A17_P6") (pintype "bidirectional"))
      (node (ref "U1") (pin "P7") (pinfunction "IO_L21P_7_P7") (pintype "bidirectional"))
    )
    (net (code "143") (name "Net-(U$6-A18)") (class "Default")
      (node (ref "U$6") (pin "P9") (pinfunction "A18_P9") (pintype "bidirectional"))
      (node (ref "U1") (pin "P10") (pinfunction "IO_L22P_7_P10") (pintype "bidirectional"))
    )
    (net (code "144") (name "Net-(U$6-DQ0)") (class "Default")
      (node (ref "U$6") (pin "P21") (pinfunction "DQ0_P21") (pintype "bidirectional"))
      (node (ref "U1") (pin "P25") (pinfunction "IO_L23P_6_P25") (pintype "bidirectional"))
    )
    (net (code "145") (name "Net-(U$6-DQ1)") (class "Default")
      (node (ref "U$6") (pin "P22") (pinfunction "DQ1_P22") (pintype "bidirectional"))
      (node (ref "U1") (pin "P26") (pinfunction "IO_L23N_6_P26") (pintype "bidirectional"))
    )
    (net (code "146") (name "Net-(U$6-DQ2)") (class "Default")
      (node (ref "U$6") (pin "P23") (pinfunction "DQ2_P23") (pintype "bidirectional"))
      (node (ref "U1") (pin "P27") (pinfunction "IO_L22P_6_P27") (pintype "bidirectional"))
    )
    (net (code "147") (name "Net-(U$6-DQ3)") (class "Default")
      (node (ref "U$6") (pin "P25") (pinfunction "DQ3_P25") (pintype "bidirectional"))
      (node (ref "U1") (pin "P28") (pinfunction "IO_L22N_6_P28") (pintype "bidirectional"))
    )
    (net (code "148") (name "Net-(U$6-DQ4)") (class "Default")
      (node (ref "U$6") (pin "P26") (pinfunction "DQ4_P26") (pintype "bidirectional"))
      (node (ref "U1") (pin "P30") (pinfunction "IO_L21P_6_P30") (pintype "bidirectional"))
    )
    (net (code "149") (name "Net-(U$6-DQ5)") (class "Default")
      (node (ref "U$6") (pin "P27") (pinfunction "DQ5_P27") (pintype "bidirectional"))
      (node (ref "U1") (pin "P31") (pinfunction "IO_L21N_6_P31") (pintype "bidirectional"))
    )
    (net (code "150") (name "Net-(U$6-DQ6)") (class "Default")
      (node (ref "U$6") (pin "P28") (pinfunction "DQ6_P28") (pintype "bidirectional"))
      (node (ref "U1") (pin "P32") (pinfunction "IO_L20P_6_P32") (pintype "bidirectional"))
    )
    (net (code "151") (name "Net-(U$6-DQ7)") (class "Default")
      (node (ref "U$6") (pin "P29") (pinfunction "DQ7_P29") (pintype "bidirectional"))
      (node (ref "U1") (pin "P33") (pinfunction "IO_L20N_6_P33") (pintype "bidirectional"))
    )
    (net (code "152") (name "Net-(U$6-OE)") (class "Default")
      (node (ref "U$6") (pin "P32") (pinfunction "OE_P32") (pintype "bidirectional"))
      (node (ref "U1") (pin "P36") (pinfunction "IO_L01N_6VRP_6_P36") (pintype "bidirectional"))
    )
    (net (code "153") (name "Net-(U$6-WE)") (class "Default")
      (node (ref "U$6") (pin "P5") (pinfunction "WE_P5") (pintype "bidirectional"))
      (node (ref "U1") (pin "P6") (pinfunction "IO_L20N_7_P6") (pintype "bidirectional"))
    )
    (net (code "154") (name "Net-(U1A-IO_L27N_0)") (class "Default")
      (node (ref "SV3") (pin "3") (pinfunction "3_3") (pintype "passive"))
      (node (ref "U1") (pin "P137") (pinfunction "IO_L27N_0_P137") (pintype "bidirectional"))
    )
    (net (code "155") (name "Net-(U1A-IO_L27P_0)") (class "Default")
      (node (ref "SV3") (pin "4") (pinfunction "4_4") (pintype "passive"))
      (node (ref "U1") (pin "P135") (pinfunction "IO_L27P_0_P135") (pintype "bidirectional"))
    )
    (net (code "156") (name "Net-(U1A-IO_L30N_0)") (class "Default")
      (node (ref "SV3") (pin "5") (pinfunction "5_5") (pintype "passive"))
      (node (ref "U1") (pin "P132") (pinfunction "IO_L30N_0_P132") (pintype "bidirectional"))
    )
    (net (code "157") (name "Net-(U1A-IO_L31N_0)") (class "Default")
      (node (ref "SV3") (pin "6") (pinfunction "6_6") (pintype "passive"))
      (node (ref "U1") (pin "P130") (pinfunction "IO_L31N_0_P130") (pintype "bidirectional"))
    )
    (net (code "158") (name "Net-(U1A-IO_L31P_0VREF_0)") (class "Default")
      (node (ref "SV3") (pin "7") (pinfunction "7_7") (pintype "passive"))
      (node (ref "U1") (pin "P129") (pinfunction "IO_L31P_0VREF_0_P129") (pintype "bidirectional"))
    )
    (net (code "159") (name "Net-(U1A-IO_L32N_0GCLK7)") (class "Default")
      (node (ref "SV3") (pin "8") (pinfunction "8_8") (pintype "passive"))
      (node (ref "U1") (pin "P128") (pinfunction "IO_L32N_0GCLK7_P128") (pintype "bidirectional"))
    )
    (net (code "160") (name "Net-(U1A-IO_L32P_0GCLK6)") (class "Default")
      (node (ref "SV3") (pin "9") (pinfunction "9_9") (pintype "passive"))
      (node (ref "U1") (pin "P127") (pinfunction "IO_L32P_0GCLK6_P127") (pintype "bidirectional"))
    )
    (net (code "161") (name "Net-(U1C-IO_L31N_1VREF_1)") (class "Default")
      (node (ref "SV3") (pin "10") (pinfunction "10_10") (pintype "passive"))
      (node (ref "U1") (pin "P123") (pinfunction "IO_L31N_1VREF_1_P123") (pintype "bidirectional"))
    )
    (net (code "162") (name "Net-(U1N-TCK)") (class "Default")
      (node (ref "R2") (pin "1") (pinfunction "1_1") (pintype "passive"))
      (node (ref "U1") (pin "P110") (pinfunction "TCK_P110") (pintype "bidirectional"))
    )
    (net (code "163") (name "Net-(U1N-TDI)") (class "Default")
      (node (ref "R1") (pin "1") (pinfunction "1_1") (pintype "passive"))
      (node (ref "U1") (pin "P144") (pinfunction "TDI_P144") (pintype "bidirectional"))
    )
    (net (code "164") (name "Net-(U1N-TMS)") (class "Default")
      (node (ref "R3") (pin "1") (pinfunction "1_1") (pintype "passive"))
      (node (ref "U1") (pin "P111") (pinfunction "TMS_P111") (pintype "bidirectional"))
    )
    (net (code "165") (name "unconnected-(IC1-NC.1-Pad2)") (class "Default")
      (node (ref "IC1") (pin "2") (pinfunction "NC.1_2") (pintype "bidirectional"))
    )
    (net (code "166") (name "unconnected-(IC1-NC.2-Pad9)") (class "Default")
      (node (ref "IC1") (pin "9") (pinfunction "NC.2_9") (pintype "bidirectional"))
    )
    (net (code "167") (name "unconnected-(IC1-NC.3-Pad12)") (class "Default")
      (node (ref "IC1") (pin "12") (pinfunction "NC.3_12") (pintype "bidirectional"))
    )
    (net (code "168") (name "unconnected-(IC1-NC.4-Pad14)") (class "Default")
      (node (ref "IC1") (pin "14") (pinfunction "NC.4_14") (pintype "bidirectional"))
    )
    (net (code "169") (name "unconnected-(IC1-NC.5-Pad15)") (class "Default")
      (node (ref "IC1") (pin "15") (pinfunction "NC.5_15") (pintype "bidirectional"))
    )
    (net (code "170") (name "unconnected-(IC1-NC.6-Pad16)") (class "Default")
      (node (ref "IC1") (pin "16") (pinfunction "NC.6_16") (pintype "bidirectional"))
    )
    (net (code "171") (name "unconnected-(IC1-{slash}CEO-Pad13)") (class "Default")
      (node (ref "IC1") (pin "13") (pinfunction "/CEO_13") (pintype "bidirectional"))
    )
    (net (code "172") (name "unconnected-(JP1-Pad3)") (class "Default")
      (node (ref "JP1") (pin "3") (pinfunction "3_3") (pintype "passive"))
    )
    (net (code "173") (name "unconnected-(JP1-Pad4)") (class "Default")
      (node (ref "JP1") (pin "4") (pinfunction "4_4") (pintype "passive"))
    )
    (net (code "174") (name "unconnected-(JP1-Pad5)") (class "Default")
      (node (ref "JP1") (pin "5") (pinfunction "5_5") (pintype "passive"))
    )
    (net (code "175") (name "unconnected-(JP1-Pad6)") (class "Default")
      (node (ref "JP1") (pin "6") (pinfunction "6_6") (pintype "passive"))
    )
    (net (code "176") (name "unconnected-(JP1-Pad7)") (class "Default")
      (node (ref "JP1") (pin "7") (pinfunction "7_7") (pintype "passive"))
    )
    (net (code "177") (name "unconnected-(JP1-Pad8)") (class "Default")
      (node (ref "JP1") (pin "8") (pinfunction "8_8") (pintype "passive"))
    )
    (net (code "178") (name "unconnected-(JP1-Pad9)") (class "Default")
      (node (ref "JP1") (pin "9") (pinfunction "9_9") (pintype "passive"))
    )
    (net (code "179") (name "unconnected-(JP1-Pad10)") (class "Default")
      (node (ref "JP1") (pin "10") (pinfunction "10_10") (pintype "passive"))
    )
    (net (code "180") (name "unconnected-(JP1-Pad11)") (class "Default")
      (node (ref "JP1") (pin "11") (pinfunction "11_11") (pintype "passive"))
    )
    (net (code "181") (name "unconnected-(JP1-Pad12)") (class "Default")
      (node (ref "JP1") (pin "12") (pinfunction "12_12") (pintype "passive"))
    )
    (net (code "182") (name "unconnected-(JP1-Pad13)") (class "Default")
      (node (ref "JP1") (pin "13") (pinfunction "13_13") (pintype "passive"))
    )
    (net (code "183") (name "unconnected-(JP1-Pad14)") (class "Default")
      (node (ref "JP1") (pin "14") (pinfunction "14_14") (pintype "passive"))
    )
    (net (code "184") (name "unconnected-(JP1-Pad15)") (class "Default")
      (node (ref "JP1") (pin "15") (pinfunction "15_15") (pintype "passive"))
    )
    (net (code "185") (name "unconnected-(JP1-Pad16)") (class "Default")
      (node (ref "JP1") (pin "16") (pinfunction "16_16") (pintype "passive"))
    )
    (net (code "186") (name "unconnected-(JP1-Pad17)") (class "Default")
      (node (ref "JP1") (pin "17") (pinfunction "17_17") (pintype "passive"))
    )
    (net (code "187") (name "unconnected-(JP1-Pad18)") (class "Default")
      (node (ref "JP1") (pin "18") (pinfunction "18_18") (pintype "passive"))
    )
    (net (code "188") (name "unconnected-(JP1-Pad19)") (class "Default")
      (node (ref "JP1") (pin "19") (pinfunction "19_19") (pintype "passive"))
    )
    (net (code "189") (name "unconnected-(JP1-Pad20)") (class "Default")
      (node (ref "JP1") (pin "20") (pinfunction "20_20") (pintype "passive"))
    )
    (net (code "190") (name "unconnected-(REG1.2-VOUT2-Pad2)") (class "Default")
      (node (ref "REG1.2") (pin "2") (pinfunction "VOUT2_2") (pintype "bidirectional"))
    )
    (net (code "191") (name "unconnected-(REG2.5-VOUT2-Pad2)") (class "Default")
      (node (ref "REG2.5") (pin "2") (pinfunction "VOUT2_2") (pintype "bidirectional"))
    )
    (net (code "192") (name "unconnected-(U$2-TRI-PadENA)") (class "Default")
      (node (ref "U$2") (pin "ENA") (pinfunction "TRI_ENA") (pintype "input"))
    )
    (net (code "193") (name "unconnected-(U$3-CARD_DETECT-PadCD)") (class "Default")
      (node (ref "U$3") (pin "CD") (pinfunction "CARD_DETECT_CD") (pintype "passive"))
    )
    (net (code "194") (name "unconnected-(U$3-DAT1-Pad8)") (class "Default")
      (node (ref "U$3") (pin "8") (pinfunction "DAT1_8") (pintype "bidirectional"))
    )
    (net (code "195") (name "unconnected-(U$3-DAT2-Pad9)") (class "Default")
      (node (ref "U$3") (pin "9") (pinfunction "DAT2_9") (pintype "bidirectional"))
    )
    (net (code "196") (name "unconnected-(U$3-WRITE_PROTECT-PadWP)") (class "Default")
      (node (ref "U$3") (pin "WP") (pinfunction "WRITE_PROTECT_WP") (pintype "passive"))
    )
    (net (code "197") (name "unconnected-(U$4-VOUT2-Pad2)") (class "Default")
      (node (ref "U$4") (pin "2") (pinfunction "VOUT2_2") (pintype "bidirectional"))
    )
    (net (code "198") (name "unconnected-(U1F-IO_L24P_3-PadP86)") (class "Default")
      (node (ref "U1") (pin "P86") (pinfunction "IO_L24P_3_P86") (pintype "bidirectional"))
    )
    (net (code "199") (name "unconnected-(U1N-HSWAP_EN-PadP142)") (class "Default")
      (node (ref "U1") (pin "P142") (pinfunction "HSWAP_EN_P142") (pintype "bidirectional"))
    )
    (net (code "200") (name "unconnected-(X1-Pad10)") (class "Default")
      (node (ref "X1") (pin "10") (pinfunction "10_10") (pintype "passive"))
    )
    (net (code "201") (name "unconnected-(X1-Pad12)") (class "Default")
      (node (ref "X1") (pin "12") (pinfunction "12_12") (pintype "passive"))
    )
    (net (code "202") (name "unconnected-(X3-Pad2)") (class "Default")
      (node (ref "X3") (pin "2") (pinfunction "2_2") (pintype "passive"))
    )
    (net (code "203") (name "unconnected-(X3-Pad8)") (class "Default")
      (node (ref "X3") (pin "8") (pinfunction "8_8") (pintype "passive"))
    )
    (net (code "204") (name "unconnected-(X4-PadG2)") (class "Default")
      (node (ref "X4") (pin "G2") (pinfunction "G2_G2") (pintype "passive"))
    )
    (net (code "205") (name "unconnected-(X5-PadG2)") (class "Default")
      (node (ref "X5") (pin "G2") (pinfunction "G2_G2") (pintype "passive"))
    )
    (net (code "206") (name "unconnected-(X6-Pad1)") (class "Default")
      (node (ref "X6") (pin "1") (pinfunction "1_1") (pintype "passive"))
    )
  )
)
